# LS1C300B_176A_Msystem.net
KiCad netlist of a schematic drawn in Altium Designer
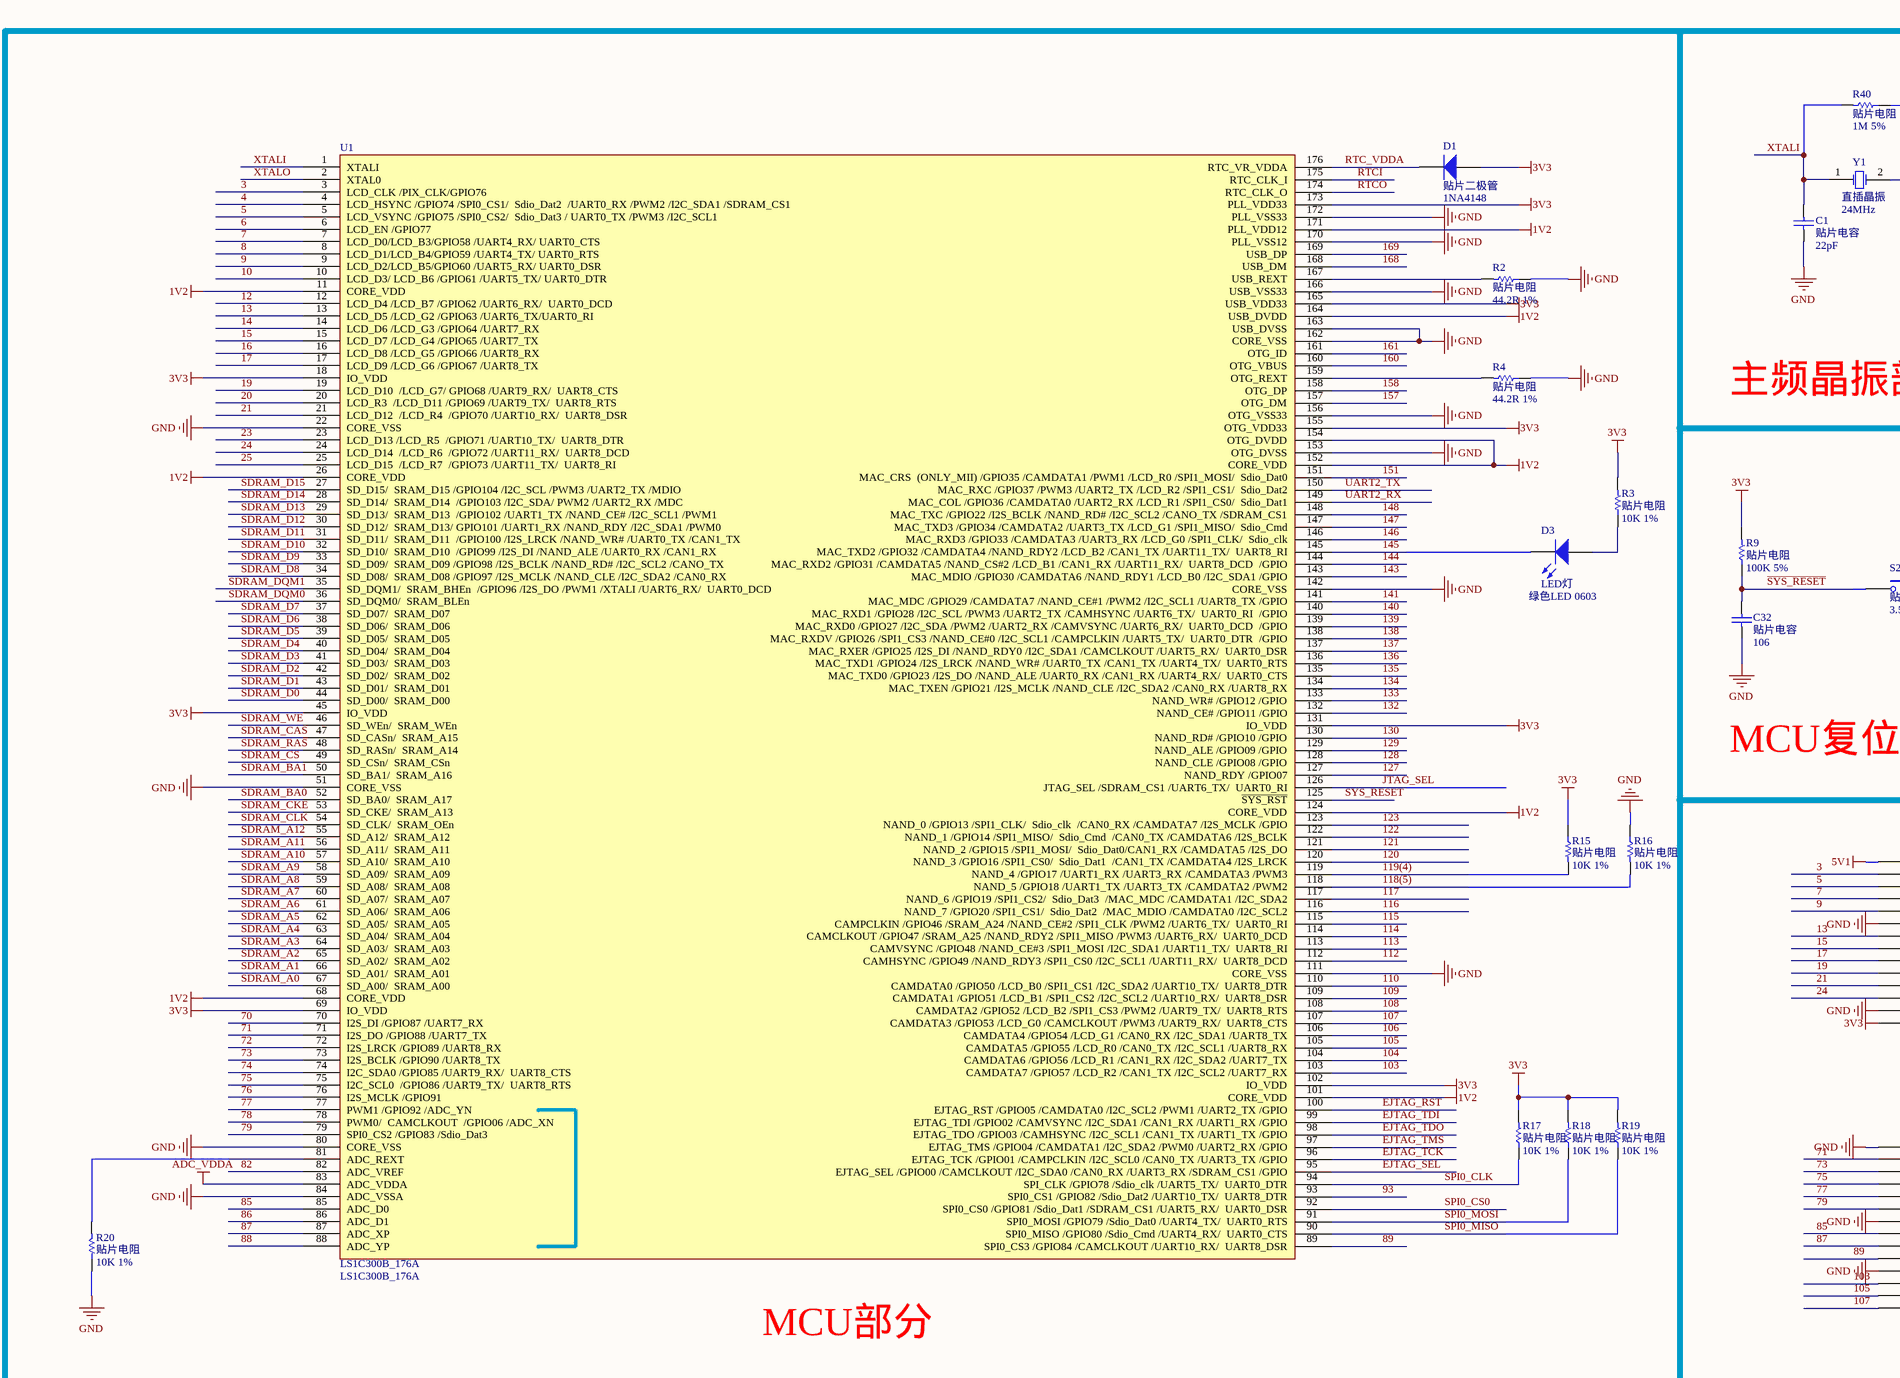
[diagram p0: LS1C300B_176A_Msystem.SchDoc, top left]
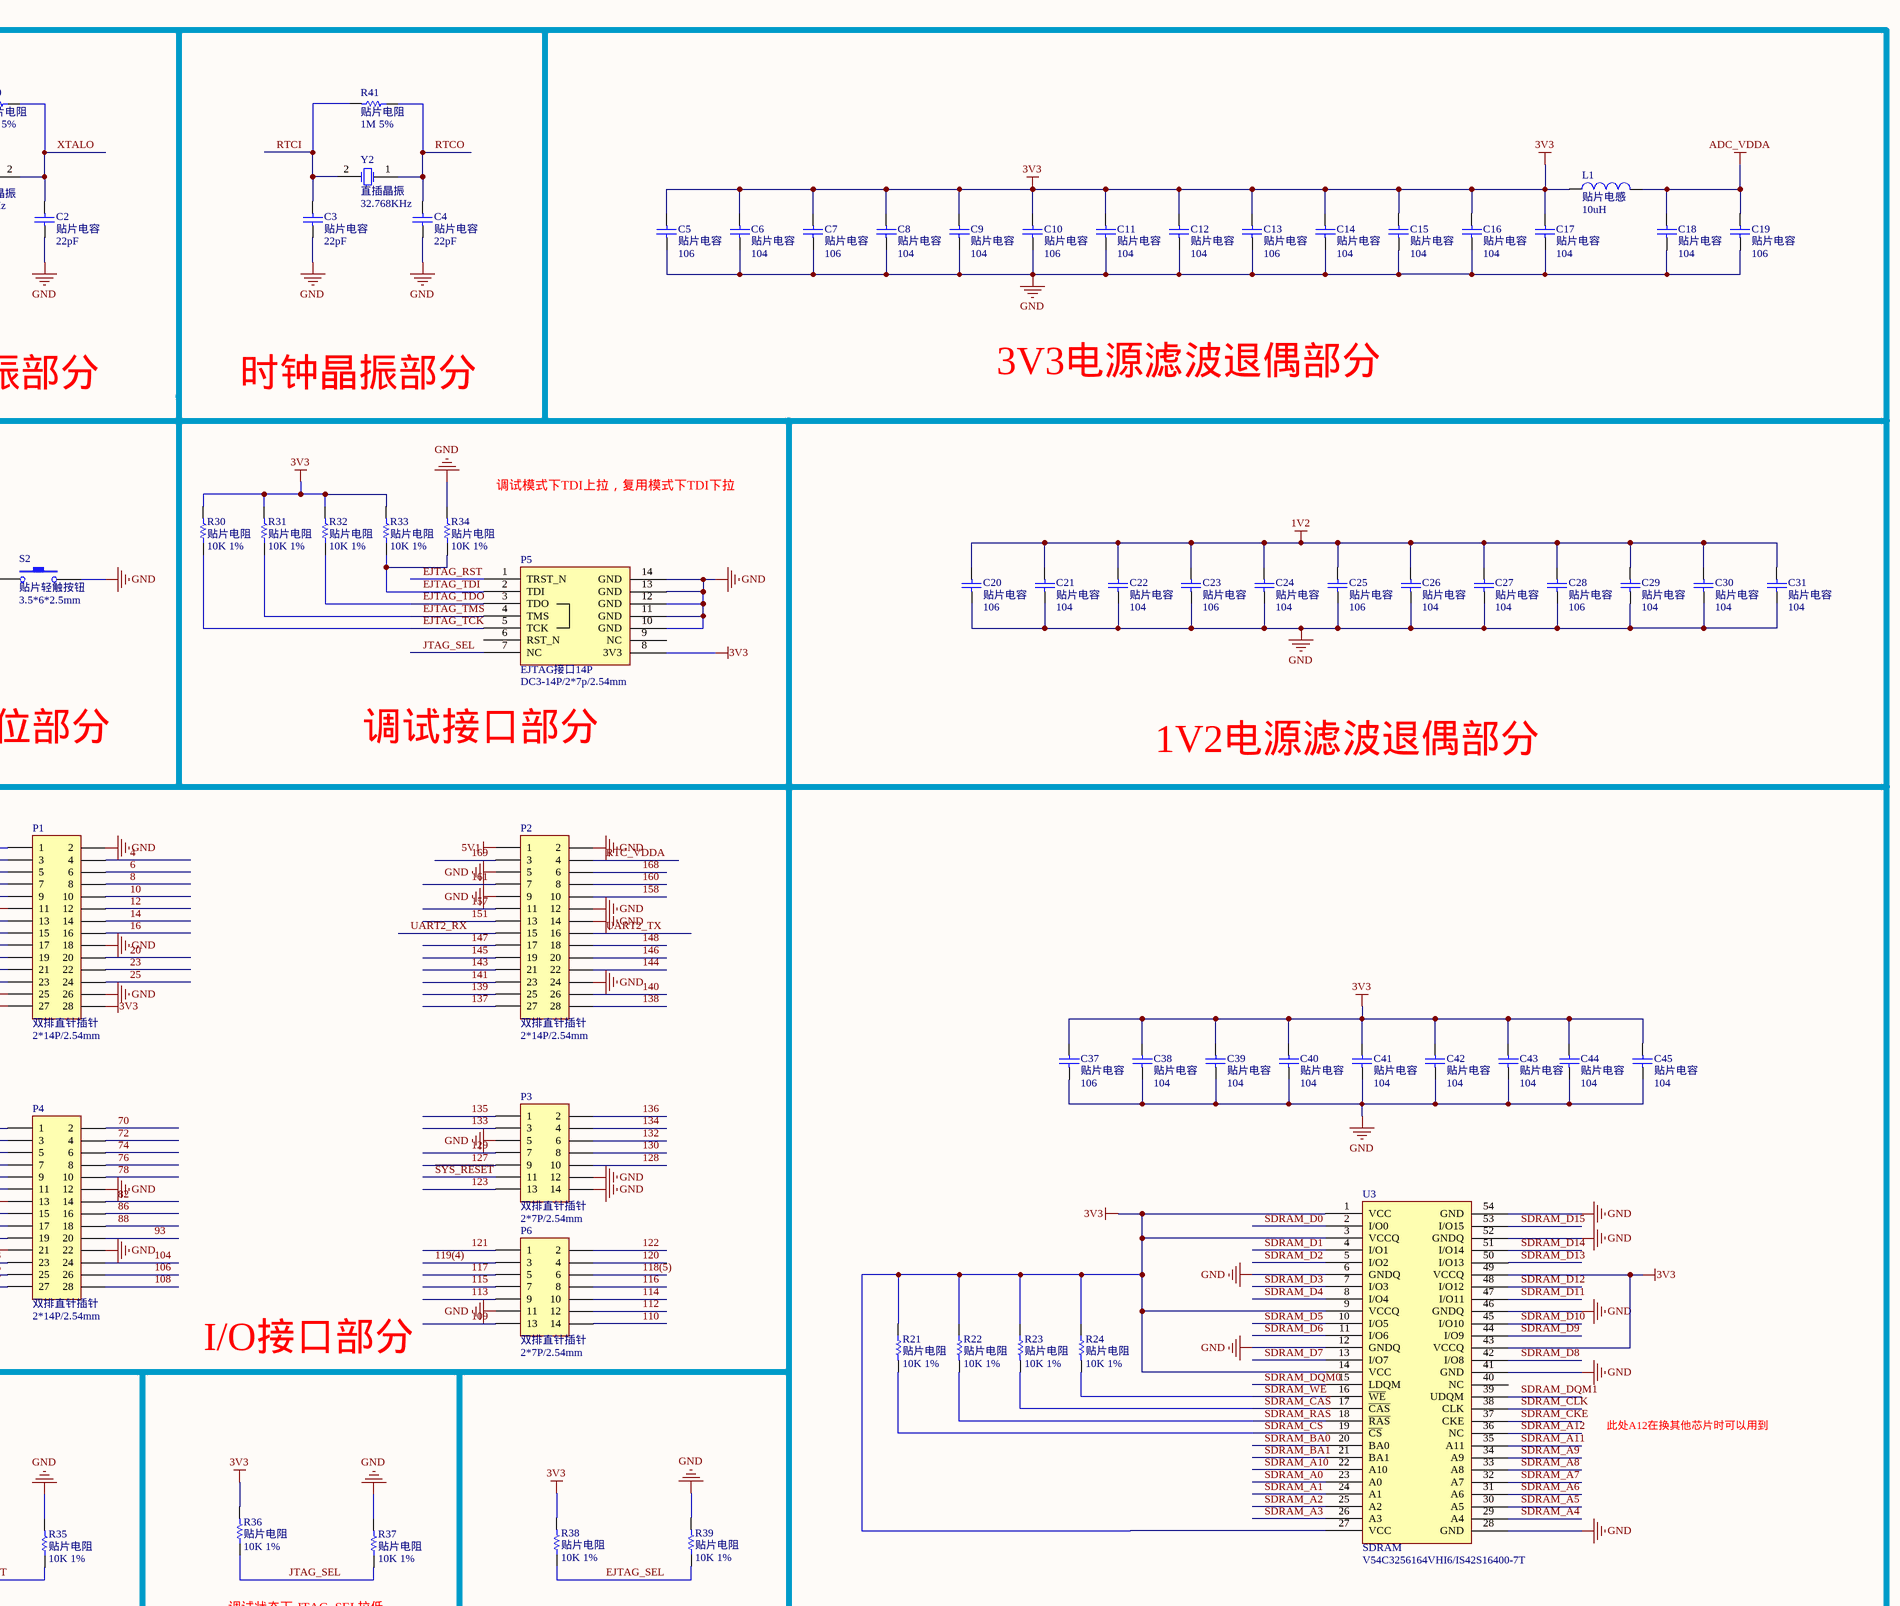
[diagram p1: LS1C300B_176A_Msystem.SchDoc, top right]
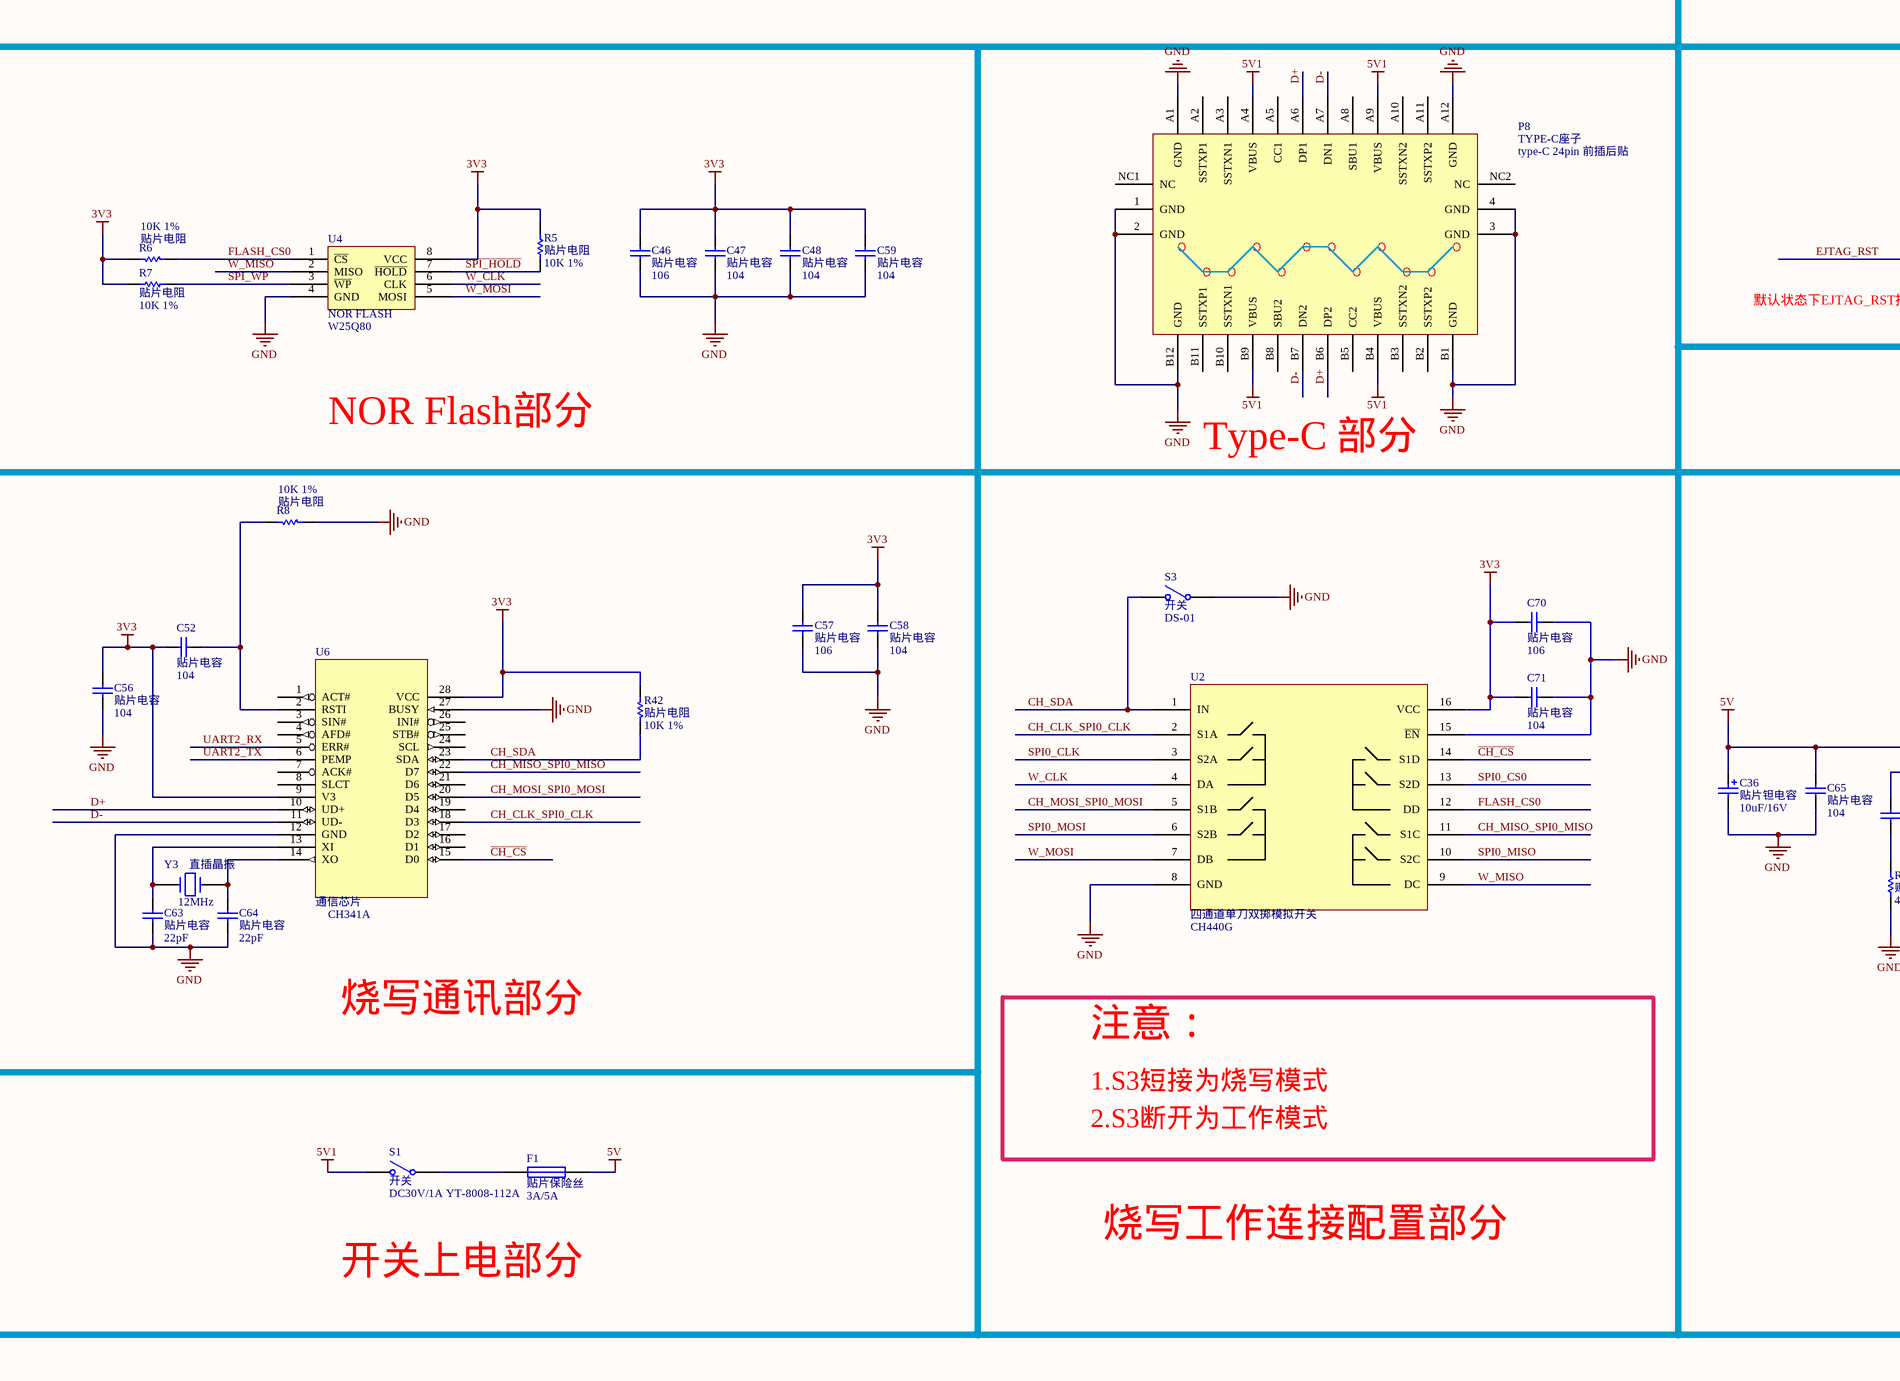
[diagram p2: LS1C300B_176A_Msystem.SchDoc, bottom left]
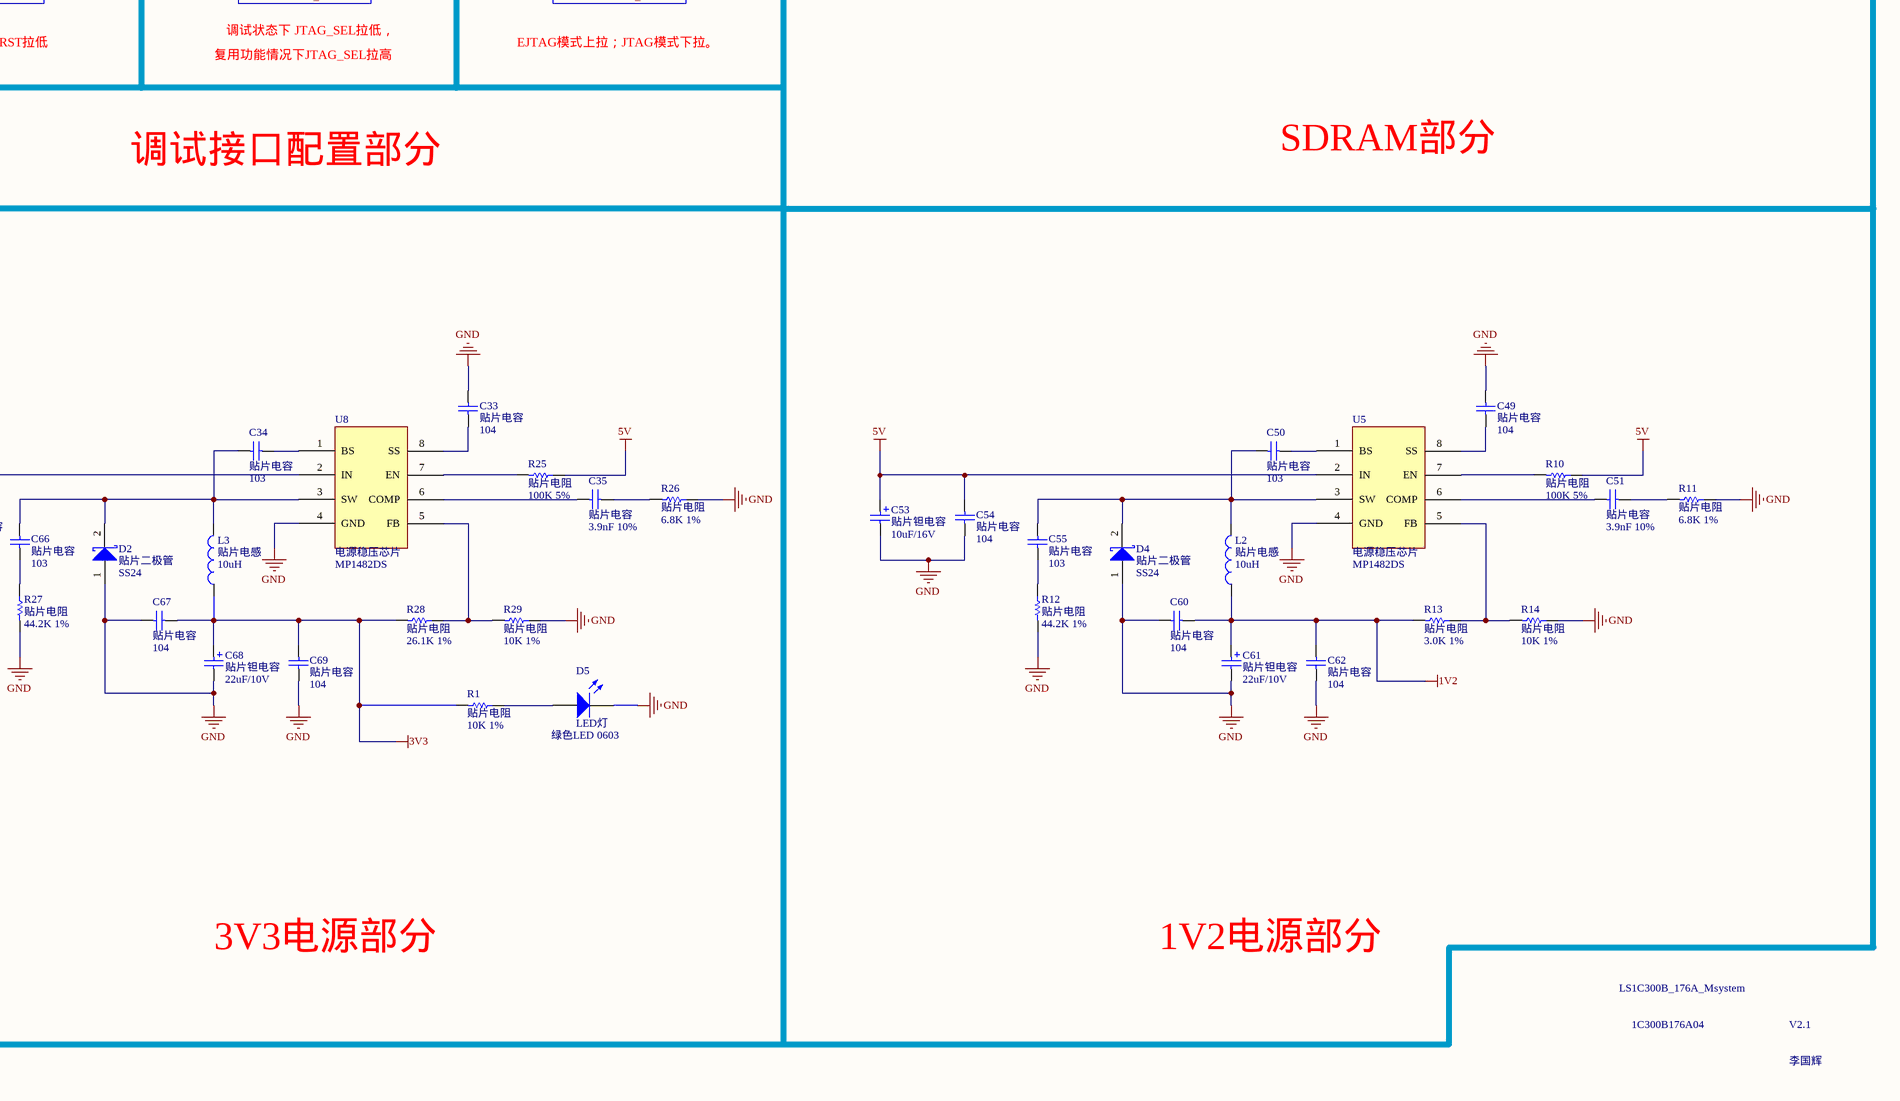
[diagram p3: LS1C300B_176A_Msystem.SchDoc, bottom right]

(export (version "E")
  (design (tool "Eeschema 10.0.6"))
  (components
    (comp (ref "C1")
      (value "贴片电容")
      (footprint "liguohui:C0603")
      (description "Capacitor")
      (fields (field (name "ALTIUM_VALUE") "22pF") (field (name "PUBLISHER") "Altium Limited"))
      (libsource (lib "Miscellaneous Devices") (part "Cap"))
    )
    (comp (ref "C2")
      (value "贴片电容")
      (footprint "liguohui:C0603")
      (description "Capacitor")
      (fields (field (name "ALTIUM_VALUE") "22pF") (field (name "PUBLISHER") "Altium Limited"))
      (libsource (lib "Miscellaneous Devices") (part "Cap"))
    )
    (comp (ref "C3")
      (value "贴片电容")
      (footprint "C0603")
      (description "Capacitor")
      (fields (field (name "ALTIUM_VALUE") "22pF") (field (name "PUBLISHER") "Altium Limited"))
      (libsource (lib "Miscellaneous Devices") (part "Cap"))
    )
    (comp (ref "C4")
      (value "贴片电容")
      (footprint "C0603")
      (description "Capacitor")
      (fields (field (name "ALTIUM_VALUE") "22pF") (field (name "PUBLISHER") "Altium Limited"))
      (libsource (lib "Miscellaneous Devices") (part "Cap"))
    )
    (comp (ref "C5")
      (value "贴片电容")
      (footprint "C0603")
      (description "Capacitor")
      (fields (field (name "ALTIUM_VALUE") "106") (field (name "PUBLISHER") "Altium Limited"))
      (libsource (lib "Miscellaneous Devices") (part "Cap"))
    )
    (comp (ref "C6")
      (value "贴片电容")
      (footprint "C0603")
      (description "Capacitor")
      (fields (field (name "ALTIUM_VALUE") "104") (field (name "PUBLISHER") "Altium Limited"))
      (libsource (lib "Miscellaneous Devices") (part "Cap"))
    )
    (comp (ref "C7")
      (value "贴片电容")
      (footprint "C0603")
      (description "Capacitor")
      (fields (field (name "ALTIUM_VALUE") "106") (field (name "PUBLISHER") "Altium Limited"))
      (libsource (lib "Miscellaneous Devices") (part "Cap"))
    )
    (comp (ref "C8")
      (value "贴片电容")
      (footprint "C0603")
      (description "Capacitor")
      (fields (field (name "ALTIUM_VALUE") "104") (field (name "PUBLISHER") "Altium Limited"))
      (libsource (lib "Miscellaneous Devices") (part "Cap"))
    )
    (comp (ref "C9")
      (value "贴片电容")
      (footprint "C0603")
      (description "Capacitor")
      (fields (field (name "ALTIUM_VALUE") "104") (field (name "PUBLISHER") "Altium Limited"))
      (libsource (lib "Miscellaneous Devices") (part "Cap"))
    )
    (comp (ref "C10")
      (value "贴片电容")
      (footprint "C0603")
      (description "Capacitor")
      (fields (field (name "ALTIUM_VALUE") "106") (field (name "PUBLISHER") "Altium Limited"))
      (libsource (lib "Miscellaneous Devices") (part "Cap"))
    )
    (comp (ref "C11")
      (value "贴片电容")
      (footprint "C0603")
      (description "Capacitor")
      (fields (field (name "ALTIUM_VALUE") "104") (field (name "PUBLISHER") "Altium Limited"))
      (libsource (lib "Miscellaneous Devices") (part "Cap"))
    )
    (comp (ref "C12")
      (value "贴片电容")
      (footprint "C0603")
      (description "Capacitor")
      (fields (field (name "ALTIUM_VALUE") "104") (field (name "PUBLISHER") "Altium Limited"))
      (libsource (lib "Miscellaneous Devices") (part "Cap"))
    )
    (comp (ref "C13")
      (value "贴片电容")
      (footprint "C0603")
      (description "Capacitor")
      (fields (field (name "ALTIUM_VALUE") "106") (field (name "PUBLISHER") "Altium Limited"))
      (libsource (lib "Miscellaneous Devices") (part "Cap"))
    )
    (comp (ref "C14")
      (value "贴片电容")
      (footprint "C0603")
      (description "Capacitor")
      (fields (field (name "ALTIUM_VALUE") "104") (field (name "PUBLISHER") "Altium Limited"))
      (libsource (lib "Miscellaneous Devices") (part "Cap"))
    )
    (comp (ref "C15")
      (value "贴片电容")
      (footprint "C0603")
      (description "Capacitor")
      (fields (field (name "ALTIUM_VALUE") "104") (field (name "PUBLISHER") "Altium Limited"))
      (libsource (lib "Miscellaneous Devices") (part "Cap"))
    )
    (comp (ref "C16")
      (value "贴片电容")
      (footprint "C0603")
      (description "Capacitor")
      (fields (field (name "ALTIUM_VALUE") "104") (field (name "PUBLISHER") "Altium Limited"))
      (libsource (lib "Miscellaneous Devices") (part "Cap"))
    )
    (comp (ref "C17")
      (value "贴片电容")
      (footprint "C0603")
      (description "Capacitor")
      (fields (field (name "ALTIUM_VALUE") "104") (field (name "PUBLISHER") "Altium Limited"))
      (libsource (lib "Miscellaneous Devices") (part "Cap"))
    )
    (comp (ref "C18")
      (value "贴片电容")
      (footprint "C0603")
      (description "Capacitor")
      (fields (field (name "ALTIUM_VALUE") "104") (field (name "PUBLISHER") "Altium Limited"))
      (libsource (lib "Miscellaneous Devices") (part "Cap"))
    )
    (comp (ref "C19")
      (value "贴片电容")
      (footprint "C0603")
      (description "Capacitor")
      (fields (field (name "ALTIUM_VALUE") "106") (field (name "PUBLISHER") "Altium Limited"))
      (libsource (lib "Miscellaneous Devices") (part "Cap"))
    )
    (comp (ref "C20")
      (value "贴片电容")
      (footprint "C0603")
      (description "Capacitor")
      (fields (field (name "ALTIUM_VALUE") "106") (field (name "PUBLISHER") "Altium Limited"))
      (libsource (lib "Miscellaneous Devices") (part "Cap"))
    )
    (comp (ref "C21")
      (value "贴片电容")
      (footprint "C0603")
      (description "Capacitor")
      (fields (field (name "ALTIUM_VALUE") "104") (field (name "PUBLISHER") "Altium Limited"))
      (libsource (lib "Miscellaneous Devices") (part "Cap"))
    )
    (comp (ref "C22")
      (value "贴片电容")
      (footprint "C0603")
      (description "Capacitor")
      (fields (field (name "ALTIUM_VALUE") "104") (field (name "PUBLISHER") "Altium Limited"))
      (libsource (lib "Miscellaneous Devices") (part "Cap"))
    )
    (comp (ref "C23")
      (value "贴片电容")
      (footprint "C0603")
      (description "Capacitor")
      (fields (field (name "ALTIUM_VALUE") "106") (field (name "PUBLISHER") "Altium Limited"))
      (libsource (lib "Miscellaneous Devices") (part "Cap"))
    )
    (comp (ref "C24")
      (value "贴片电容")
      (footprint "C0603")
      (description "Capacitor")
      (fields (field (name "ALTIUM_VALUE") "104") (field (name "PUBLISHER") "Altium Limited"))
      (libsource (lib "Miscellaneous Devices") (part "Cap"))
    )
    (comp (ref "C25")
      (value "贴片电容")
      (footprint "C0603")
      (description "Capacitor")
      (fields (field (name "ALTIUM_VALUE") "106") (field (name "PUBLISHER") "Altium Limited"))
      (libsource (lib "Miscellaneous Devices") (part "Cap"))
    )
    (comp (ref "C26")
      (value "贴片电容")
      (footprint "C0603")
      (description "Capacitor")
      (fields (field (name "ALTIUM_VALUE") "104") (field (name "PUBLISHER") "Altium Limited"))
      (libsource (lib "Miscellaneous Devices") (part "Cap"))
    )
    (comp (ref "C27")
      (value "贴片电容")
      (footprint "C0603")
      (description "Capacitor")
      (fields (field (name "ALTIUM_VALUE") "104") (field (name "PUBLISHER") "Altium Limited"))
      (libsource (lib "Miscellaneous Devices") (part "Cap"))
    )
    (comp (ref "C28")
      (value "贴片电容")
      (footprint "C0603")
      (description "Capacitor")
      (fields (field (name "ALTIUM_VALUE") "106") (field (name "PUBLISHER") "Altium Limited"))
      (libsource (lib "Miscellaneous Devices") (part "Cap"))
    )
    (comp (ref "C29")
      (value "贴片电容")
      (footprint "C0603")
      (description "Capacitor")
      (fields (field (name "ALTIUM_VALUE") "104") (field (name "PUBLISHER") "Altium Limited"))
      (libsource (lib "Miscellaneous Devices") (part "Cap"))
    )
    (comp (ref "C30")
      (value "贴片电容")
      (footprint "C0603")
      (description "Capacitor")
      (fields (field (name "ALTIUM_VALUE") "104") (field (name "PUBLISHER") "Altium Limited"))
      (libsource (lib "Miscellaneous Devices") (part "Cap"))
    )
    (comp (ref "C31")
      (value "贴片电容")
      (footprint "C0603")
      (description "Capacitor")
      (fields (field (name "ALTIUM_VALUE") "104") (field (name "PUBLISHER") "Altium Limited"))
      (libsource (lib "Miscellaneous Devices") (part "Cap"))
    )
    (comp (ref "C32")
      (value "贴片电容")
      (footprint "C0603")
      (description "Capacitor")
      (fields (field (name "ALTIUM_VALUE") "106") (field (name "PUBLISHER") "Altium Limited"))
      (libsource (lib "Miscellaneous Devices") (part "Cap"))
    )
    (comp (ref "C33")
      (value "贴片电容")
      (footprint "C0603")
      (description "Capacitor")
      (fields (field (name "ALTIUM_VALUE") "104") (field (name "PUBLISHER") "Altium Limited"))
      (libsource (lib "Miscellaneous Devices") (part "Cap"))
    )
    (comp (ref "C34")
      (value "贴片电容")
      (footprint "C0603")
      (description "Capacitor")
      (fields (field (name "ALTIUM_VALUE") "103") (field (name "PUBLISHER") "Altium Limited"))
      (libsource (lib "Miscellaneous Devices") (part "Cap"))
    )
    (comp (ref "C35")
      (value "贴片电容")
      (footprint "C0603")
      (description "Capacitor")
      (fields (field (name "ALTIUM_VALUE") "3.9nF 10%") (field (name "PUBLISHER") "Altium Limited"))
      (libsource (lib "Miscellaneous Devices") (part "Cap"))
    )
    (comp (ref "C36")
      (value "贴片钽电容")
      (footprint "P-C1206")
      (description "Polarized Capacitor (Axial)")
      (fields (field (name "ALTIUM_VALUE") "10uF/16V") (field (name "PUBLISHER") "Altium Limited"))
      (libsource (lib "Miscellaneous Devices") (part "Cap Pol2"))
    )
    (comp (ref "C37")
      (value "贴片电容")
      (footprint "C0603")
      (description "Capacitor")
      (fields (field (name "ALTIUM_VALUE") "106") (field (name "PUBLISHER") "Altium Limited"))
      (libsource (lib "Miscellaneous Devices") (part "Cap"))
    )
    (comp (ref "C38")
      (value "贴片电容")
      (footprint "C0603")
      (description "Capacitor")
      (fields (field (name "ALTIUM_VALUE") "104") (field (name "PUBLISHER") "Altium Limited"))
      (libsource (lib "Miscellaneous Devices") (part "Cap"))
    )
    (comp (ref "C39")
      (value "贴片电容")
      (footprint "C0603")
      (description "Capacitor")
      (fields (field (name "ALTIUM_VALUE") "104") (field (name "PUBLISHER") "Altium Limited"))
      (libsource (lib "Miscellaneous Devices") (part "Cap"))
    )
    (comp (ref "C40")
      (value "贴片电容")
      (footprint "C0603")
      (description "Capacitor")
      (fields (field (name "ALTIUM_VALUE") "104") (field (name "PUBLISHER") "Altium Limited"))
      (libsource (lib "Miscellaneous Devices") (part "Cap"))
    )
    (comp (ref "C41")
      (value "贴片电容")
      (footprint "C0603")
      (description "Capacitor")
      (fields (field (name "ALTIUM_VALUE") "104") (field (name "PUBLISHER") "Altium Limited"))
      (libsource (lib "Miscellaneous Devices") (part "Cap"))
    )
    (comp (ref "C42")
      (value "贴片电容")
      (footprint "C0603")
      (description "Capacitor")
      (fields (field (name "ALTIUM_VALUE") "104") (field (name "PUBLISHER") "Altium Limited"))
      (libsource (lib "Miscellaneous Devices") (part "Cap"))
    )
    (comp (ref "C43")
      (value "贴片电容")
      (footprint "C0603")
      (description "Capacitor")
      (fields (field (name "ALTIUM_VALUE") "104") (field (name "PUBLISHER") "Altium Limited"))
      (libsource (lib "Miscellaneous Devices") (part "Cap"))
    )
    (comp (ref "C44")
      (value "贴片电容")
      (footprint "C0603")
      (description "Capacitor")
      (fields (field (name "ALTIUM_VALUE") "104") (field (name "PUBLISHER") "Altium Limited"))
      (libsource (lib "Miscellaneous Devices") (part "Cap"))
    )
    (comp (ref "C45")
      (value "贴片电容")
      (footprint "C0603")
      (description "Capacitor")
      (fields (field (name "ALTIUM_VALUE") "104") (field (name "PUBLISHER") "Altium Limited"))
      (libsource (lib "Miscellaneous Devices") (part "Cap"))
    )
    (comp (ref "C46")
      (value "贴片电容")
      (footprint "C0603")
      (description "Capacitor")
      (fields (field (name "ALTIUM_VALUE") "106") (field (name "PUBLISHER") "Altium Limited"))
      (libsource (lib "Miscellaneous Devices") (part "Cap"))
    )
    (comp (ref "C47")
      (value "贴片电容")
      (footprint "C0603")
      (description "Capacitor")
      (fields (field (name "ALTIUM_VALUE") "104") (field (name "PUBLISHER") "Altium Limited"))
      (libsource (lib "Miscellaneous Devices") (part "Cap"))
    )
    (comp (ref "C48")
      (value "贴片电容")
      (footprint "C0603")
      (description "Capacitor")
      (fields (field (name "ALTIUM_VALUE") "104") (field (name "PUBLISHER") "Altium Limited"))
      (libsource (lib "Miscellaneous Devices") (part "Cap"))
    )
    (comp (ref "C49")
      (value "贴片电容")
      (footprint "C0603")
      (description "Capacitor")
      (fields (field (name "ALTIUM_VALUE") "104") (field (name "PUBLISHER") "Altium Limited"))
      (libsource (lib "Miscellaneous Devices") (part "Cap"))
    )
    (comp (ref "C50")
      (value "贴片电容")
      (footprint "C0603")
      (description "Capacitor")
      (fields (field (name "ALTIUM_VALUE") "103") (field (name "PUBLISHER") "Altium Limited"))
      (libsource (lib "Miscellaneous Devices") (part "Cap"))
    )
    (comp (ref "C51")
      (value "贴片电容")
      (footprint "C0603")
      (description "Capacitor")
      (fields (field (name "ALTIUM_VALUE") "3.9nF 10%") (field (name "PUBLISHER") "Altium Limited"))
      (libsource (lib "Miscellaneous Devices") (part "Cap"))
    )
    (comp (ref "C52")
      (value "贴片电容")
      (footprint "C0603")
      (description "Capacitor")
      (fields (field (name "ALTIUM_VALUE") "104") (field (name "PUBLISHER") "Altium Limited"))
      (libsource (lib "Miscellaneous Devices") (part "Cap"))
    )
    (comp (ref "C53")
      (value "贴片钽电容")
      (footprint "P-C1206")
      (description "Polarized Capacitor (Axial)")
      (fields (field (name "ALTIUM_VALUE") "10uF/16V") (field (name "PUBLISHER") "Altium Limited"))
      (libsource (lib "Miscellaneous Devices") (part "Cap Pol2"))
    )
    (comp (ref "C54")
      (value "贴片电容")
      (footprint "C0603")
      (description "Capacitor")
      (fields (field (name "ALTIUM_VALUE") "104") (field (name "PUBLISHER") "Altium Limited"))
      (libsource (lib "Miscellaneous Devices") (part "Cap"))
    )
    (comp (ref "C55")
      (value "贴片电容")
      (footprint "C0603")
      (description "Capacitor")
      (fields (field (name "ALTIUM_VALUE") "103") (field (name "PUBLISHER") "Altium Limited"))
      (libsource (lib "Miscellaneous Devices") (part "Cap"))
    )
    (comp (ref "C56")
      (value "贴片电容")
      (footprint "C0603")
      (description "Capacitor")
      (fields (field (name "ALTIUM_VALUE") "104") (field (name "PUBLISHER") "Altium Limited"))
      (libsource (lib "Miscellaneous Devices") (part "Cap"))
    )
    (comp (ref "C57")
      (value "贴片电容")
      (footprint "C0603")
      (description "Capacitor")
      (fields (field (name "ALTIUM_VALUE") "106") (field (name "PUBLISHER") "Altium Limited"))
      (libsource (lib "Miscellaneous Devices") (part "Cap"))
    )
    (comp (ref "C58")
      (value "贴片电容")
      (footprint "C0603")
      (description "Capacitor")
      (fields (field (name "ALTIUM_VALUE") "104") (field (name "PUBLISHER") "Altium Limited"))
      (libsource (lib "Miscellaneous Devices") (part "Cap"))
    )
    (comp (ref "C59")
      (value "贴片电容")
      (footprint "C0603")
      (description "Capacitor")
      (fields (field (name "ALTIUM_VALUE") "104") (field (name "PUBLISHER") "Altium Limited"))
      (libsource (lib "Miscellaneous Devices") (part "Cap"))
    )
    (comp (ref "C60")
      (value "贴片电容")
      (footprint "C0603")
      (description "Capacitor")
      (fields (field (name "ALTIUM_VALUE") "104") (field (name "PUBLISHER") "Altium Limited"))
      (libsource (lib "Miscellaneous Devices") (part "Cap"))
    )
    (comp (ref "C61")
      (value "贴片钽电容")
      (footprint "P-C1206")
      (description "Polarized Capacitor (Axial)")
      (fields (field (name "ALTIUM_VALUE") "22uF/10V") (field (name "PUBLISHER") "Altium Limited"))
      (libsource (lib "Miscellaneous Devices") (part "Cap Pol2"))
    )
    (comp (ref "C62")
      (value "贴片电容")
      (footprint "C0603")
      (description "Capacitor")
      (fields (field (name "ALTIUM_VALUE") "104") (field (name "PUBLISHER") "Altium Limited"))
      (libsource (lib "Miscellaneous Devices") (part "Cap"))
    )
    (comp (ref "C63")
      (value "贴片电容")
      (footprint "C0603")
      (description "Capacitor")
      (fields (field (name "ALTIUM_VALUE") "22pF") (field (name "PUBLISHER") "Altium Limited"))
      (libsource (lib "Miscellaneous Devices") (part "Cap"))
    )
    (comp (ref "C64")
      (value "贴片电容")
      (footprint "liguohui:C0603")
      (description "Capacitor")
      (fields (field (name "ALTIUM_VALUE") "22pF") (field (name "PUBLISHER") "Altium Limited"))
      (libsource (lib "Miscellaneous Devices") (part "Cap"))
    )
    (comp (ref "C65")
      (value "贴片电容")
      (footprint "C0603")
      (description "Capacitor")
      (fields (field (name "ALTIUM_VALUE") "104") (field (name "PUBLISHER") "Altium Limited"))
      (libsource (lib "Miscellaneous Devices") (part "Cap"))
    )
    (comp (ref "C66")
      (value "贴片电容")
      (footprint "C0603")
      (description "Capacitor")
      (fields (field (name "ALTIUM_VALUE") "103") (field (name "PUBLISHER") "Altium Limited"))
      (libsource (lib "Miscellaneous Devices") (part "Cap"))
    )
    (comp (ref "C67")
      (value "贴片电容")
      (footprint "C0603")
      (description "Capacitor")
      (fields (field (name "ALTIUM_VALUE") "104") (field (name "PUBLISHER") "Altium Limited"))
      (libsource (lib "Miscellaneous Devices") (part "Cap"))
    )
    (comp (ref "C68")
      (value "贴片钽电容")
      (footprint "P-C1206")
      (description "Polarized Capacitor (Axial)")
      (fields (field (name "ALTIUM_VALUE") "22uF/10V") (field (name "PUBLISHER") "Altium Limited"))
      (libsource (lib "Miscellaneous Devices") (part "Cap Pol2"))
    )
    (comp (ref "C69")
      (value "贴片电容")
      (footprint "C0603")
      (description "Capacitor")
      (fields (field (name "ALTIUM_VALUE") "104") (field (name "PUBLISHER") "Altium Limited"))
      (libsource (lib "Miscellaneous Devices") (part "Cap"))
    )
    (comp (ref "C70")
      (value "贴片电容")
      (footprint "C0603")
      (description "Capacitor")
      (fields (field (name "ALTIUM_VALUE") "106") (field (name "PUBLISHER") "Altium Limited"))
      (libsource (lib "Miscellaneous Devices") (part "Cap"))
    )
    (comp (ref "C71")
      (value "贴片电容")
      (footprint "C0603")
      (description "Capacitor")
      (fields (field (name "ALTIUM_VALUE") "104") (field (name "PUBLISHER") "Altium Limited"))
      (libsource (lib "Miscellaneous Devices") (part "Cap"))
    )
    (comp (ref "D1")
      (value "贴片二极管")
      (footprint "LL-34")
      (description "Default Diode")
      (fields (field (name "ALTIUM_VALUE") "1NA4148") (field (name "PUBLISHER") "Altium Limited"))
      (libsource (lib "Miscellaneous Devices") (part "Diode"))
    )
    (comp (ref "D2")
      (value "贴片二极管")
      (footprint "DO-214AC")
      (fields (field (name "ALTIUM_VALUE") "SS24"))
      (libsource (lib "LGHLIB") (part "1N47xx"))
    )
    (comp (ref "D3")
      (value "LED灯")
      (footprint "LED-0603")
      (description "Typical INFRARED GaAs LED")
      (fields (field (name "ALTIUM_VALUE") "绿色LED 0603") (field (name "PUBLISHER") "Altium Limited"))
      (libsource (lib "Miscellaneous Devices") (part "LED0"))
    )
    (comp (ref "D4")
      (value "贴片二极管")
      (footprint "DO-214AC")
      (fields (field (name "ALTIUM_VALUE") "SS24"))
      (libsource (lib "LGHLIB") (part "1N47xx"))
    )
    (comp (ref "D5")
      (value "LED灯")
      (footprint "LED-0603")
      (description "Typical INFRARED GaAs LED")
      (fields (field (name "ALTIUM_VALUE") "绿色LED 0603") (field (name "PUBLISHER") "Altium Limited"))
      (libsource (lib "Miscellaneous Devices") (part "LED0"))
    )
    (comp (ref "F1")
      (value "贴片保险丝")
      (footprint "R1206")
      (description "Fuse")
      (fields (field (name "ALTIUM_VALUE") "3A/5A") (field (name "PUBLISHER") "Altium Limited"))
      (libsource (lib "Miscellaneous Devices") (part "Fuse 1"))
    )
    (comp (ref "L1")
      (value "贴片电感")
      (footprint "L0603")
      (description "Inductor")
      (fields (field (name "ALTIUM_VALUE") "10uH") (field (name "PUBLISHER") "Altium Limited"))
      (libsource (lib "Miscellaneous Devices") (part "Inductor"))
    )
    (comp (ref "L2")
      (value "贴片电感")
      (footprint "CD75")
      (description "Inductor")
      (fields (field (name "ALTIUM_VALUE") "10uH") (field (name "PUBLISHER") "Altium Limited"))
      (libsource (lib "Miscellaneous Devices") (part "Inductor"))
    )
    (comp (ref "L3")
      (value "贴片电感")
      (footprint "CD75")
      (description "Inductor")
      (fields (field (name "ALTIUM_VALUE") "10uH") (field (name "PUBLISHER") "Altium Limited"))
      (libsource (lib "Miscellaneous Devices") (part "Inductor"))
    )
    (comp (ref "P1")
      (value "双排直针插针")
      (footprint "HDR2X14")
      (description "Header, 14-Pin, Dual row")
      (fields (field (name "ALTIUM_VALUE") "2*14P/2.54mm") (field (name "PUBLISHER") "Altium Limited"))
      (libsource (lib "Miscellaneous Connectors") (part "MHDR2X14"))
    )
    (comp (ref "P2")
      (value "双排直针插针")
      (footprint "HDR2X14")
      (description "Header, 14-Pin, Dual row")
      (fields (field (name "ALTIUM_VALUE") "2*14P/2.54mm") (field (name "PUBLISHER") "Altium Limited"))
      (libsource (lib "Miscellaneous Connectors") (part "MHDR2X14"))
    )
    (comp (ref "P3")
      (value "双排直针插针")
      (footprint "HDR2X7")
      (description "Header, 7-Pin, Dual row")
      (fields (field (name "ALTIUM_VALUE") "2*7P/2.54mm") (field (name "PUBLISHER") "Altium Limited"))
      (libsource (lib "Miscellaneous Connectors") (part "MHDR2X7"))
    )
    (comp (ref "P4")
      (value "双排直针插针")
      (footprint "HDR2X14")
      (description "Header, 14-Pin, Dual row")
      (fields (field (name "ALTIUM_VALUE") "2*14P/2.54mm") (field (name "PUBLISHER") "Altium Limited"))
      (libsource (lib "Miscellaneous Connectors") (part "MHDR2X14"))
    )
    (comp (ref "P5")
      (value "EJTAG接口14P")
      (footprint "DC3-14P")
      (fields (field (name "ALTIUM_VALUE") "DC3-14P/2*7p/2.54mm"))
      (libsource (lib "LGHLIB") (part "EJTAG-14P"))
    )
    (comp (ref "P6")
      (value "双排直针插针")
      (footprint "HDR2X7")
      (description "Header, 7-Pin, Dual row")
      (fields (field (name "ALTIUM_VALUE") "2*7P/2.54mm") (field (name "PUBLISHER") "Altium Limited"))
      (libsource (lib "Miscellaneous Connectors") (part "MHDR2X7"))
    )
    (comp (ref "P8")
      (value "TYPE-C座子")
      (footprint "Type-C-24pin")
      (description "TYPE-C座子，24pin ，可用于大电流，四脚插板，前插后贴")
      (fields (field (name "ALTIUM_VALUE") "type-C 24pin 前插后贴"))
      (libsource (lib "LGHLIB") (part "Type-C-24PIN"))
    )
    (comp (ref "R1")
      (value "贴片电阻")
      (footprint "R0603")
      (description "Resistor")
      (fields (field (name "ALTIUM_VALUE") "10K 1%") (field (name "PUBLISHER") "Altium Limited"))
      (libsource (lib "Miscellaneous Devices") (part "Res1"))
    )
    (comp (ref "R2")
      (value "贴片电阻")
      (footprint "R0603")
      (description "Resistor")
      (fields (field (name "ALTIUM_VALUE") "44.2R 1%") (field (name "PUBLISHER") "Altium Limited"))
      (libsource (lib "Miscellaneous Devices") (part "Res1"))
    )
    (comp (ref "R3")
      (value "贴片电阻")
      (footprint "R0603")
      (description "Resistor")
      (fields (field (name "ALTIUM_VALUE") "10K 1%") (field (name "PUBLISHER") "Altium Limited"))
      (libsource (lib "Miscellaneous Devices") (part "Res1"))
    )
    (comp (ref "R4")
      (value "贴片电阻")
      (footprint "R0603")
      (description "Resistor")
      (fields (field (name "ALTIUM_VALUE") "44.2R 1%") (field (name "PUBLISHER") "Altium Limited"))
      (libsource (lib "Miscellaneous Devices") (part "Res1"))
    )
    (comp (ref "R5")
      (value "贴片电阻")
      (footprint "R0603")
      (description "Resistor")
      (fields (field (name "ALTIUM_VALUE") "10K 1%") (field (name "PUBLISHER") "Altium Limited"))
      (libsource (lib "Miscellaneous Devices") (part "Res1"))
    )
    (comp (ref "R6")
      (value "贴片电阻")
      (footprint "R0603")
      (description "Resistor")
      (fields (field (name "ALTIUM_VALUE") "10K 1%") (field (name "PUBLISHER") "Altium Limited"))
      (libsource (lib "Miscellaneous Devices") (part "Res1"))
    )
    (comp (ref "R7")
      (value "贴片电阻")
      (footprint "R0603")
      (description "Resistor")
      (fields (field (name "ALTIUM_VALUE") "10K 1%") (field (name "PUBLISHER") "Altium Limited"))
      (libsource (lib "Miscellaneous Devices") (part "Res1"))
    )
    (comp (ref "R8")
      (value "贴片电阻")
      (footprint "R0603")
      (description "Resistor")
      (fields (field (name "ALTIUM_VALUE") "10K 1%") (field (name "PUBLISHER") "Altium Limited"))
      (libsource (lib "Miscellaneous Devices") (part "Res1"))
    )
    (comp (ref "R9")
      (value "贴片电阻")
      (footprint "R0603")
      (description "Resistor")
      (fields (field (name "ALTIUM_VALUE") "100K 5%") (field (name "PUBLISHER") "Altium Limited"))
      (libsource (lib "Miscellaneous Devices") (part "Res1"))
    )
    (comp (ref "R10")
      (value "贴片电阻")
      (footprint "R0603")
      (description "Resistor")
      (fields (field (name "ALTIUM_VALUE") "100K 5%") (field (name "PUBLISHER") "Altium Limited"))
      (libsource (lib "Miscellaneous Devices") (part "Res1"))
    )
    (comp (ref "R11")
      (value "贴片电阻")
      (footprint "R0603")
      (description "Resistor")
      (fields (field (name "ALTIUM_VALUE") "6.8K 1%") (field (name "PUBLISHER") "Altium Limited"))
      (libsource (lib "Miscellaneous Devices") (part "Res1"))
    )
    (comp (ref "R12")
      (value "贴片电阻")
      (footprint "R0603")
      (description "Resistor")
      (fields (field (name "ALTIUM_VALUE") "44.2K 1%") (field (name "PUBLISHER") "Altium Limited"))
      (libsource (lib "Miscellaneous Devices") (part "Res1"))
    )
    (comp (ref "R13")
      (value "贴片电阻")
      (footprint "R0603")
      (description "Resistor")
      (fields (field (name "ALTIUM_VALUE") "3.0K 1%") (field (name "PUBLISHER") "Altium Limited"))
      (libsource (lib "Miscellaneous Devices") (part "Res1"))
    )
    (comp (ref "R14")
      (value "贴片电阻")
      (footprint "R0603")
      (description "Resistor")
      (fields (field (name "ALTIUM_VALUE") "10K 1%") (field (name "PUBLISHER") "Altium Limited"))
      (libsource (lib "Miscellaneous Devices") (part "Res1"))
    )
    (comp (ref "R15")
      (value "贴片电阻")
      (footprint "R0603")
      (description "Resistor")
      (fields (field (name "ALTIUM_VALUE") "10K 1%") (field (name "PUBLISHER") "Altium Limited"))
      (libsource (lib "Miscellaneous Devices") (part "Res1"))
    )
    (comp (ref "R16")
      (value "贴片电阻")
      (footprint "R0603")
      (description "Resistor")
      (fields (field (name "ALTIUM_VALUE") "10K 1%") (field (name "PUBLISHER") "Altium Limited"))
      (libsource (lib "Miscellaneous Devices") (part "Res1"))
    )
    (comp (ref "R17")
      (value "贴片电阻")
      (footprint "R0603")
      (description "Resistor")
      (fields (field (name "ALTIUM_VALUE") "10K 1%") (field (name "PUBLISHER") "Altium Limited"))
      (libsource (lib "Miscellaneous Devices") (part "Res1"))
    )
    (comp (ref "R18")
      (value "贴片电阻")
      (footprint "R0603")
      (description "Resistor")
      (fields (field (name "ALTIUM_VALUE") "10K 1%") (field (name "PUBLISHER") "Altium Limited"))
      (libsource (lib "Miscellaneous Devices") (part "Res1"))
    )
    (comp (ref "R19")
      (value "贴片电阻")
      (footprint "R0603")
      (description "Resistor")
      (fields (field (name "ALTIUM_VALUE") "10K 1%") (field (name "PUBLISHER") "Altium Limited"))
      (libsource (lib "Miscellaneous Devices") (part "Res1"))
    )
    (comp (ref "R20")
      (value "贴片电阻")
      (footprint "R0603")
      (description "Resistor")
      (fields (field (name "ALTIUM_VALUE") "10K 1%") (field (name "PUBLISHER") "Altium Limited"))
      (libsource (lib "Miscellaneous Devices") (part "Res1"))
    )
    (comp (ref "R21")
      (value "贴片电阻")
      (footprint "R0603")
      (description "Resistor")
      (fields (field (name "ALTIUM_VALUE") "10K 1%") (field (name "PUBLISHER") "Altium Limited"))
      (libsource (lib "Miscellaneous Devices") (part "Res1"))
    )
    (comp (ref "R22")
      (value "贴片电阻")
      (footprint "R0603")
      (description "Resistor")
      (fields (field (name "ALTIUM_VALUE") "10K 1%") (field (name "PUBLISHER") "Altium Limited"))
      (libsource (lib "Miscellaneous Devices") (part "Res1"))
    )
    (comp (ref "R23")
      (value "贴片电阻")
      (footprint "R0603")
      (description "Resistor")
      (fields (field (name "ALTIUM_VALUE") "10K 1%") (field (name "PUBLISHER") "Altium Limited"))
      (libsource (lib "Miscellaneous Devices") (part "Res1"))
    )
    (comp (ref "R24")
      (value "贴片电阻")
      (footprint "R0603")
      (description "Resistor")
      (fields (field (name "ALTIUM_VALUE") "10K 1%") (field (name "PUBLISHER") "Altium Limited"))
      (libsource (lib "Miscellaneous Devices") (part "Res1"))
    )
    (comp (ref "R25")
      (value "贴片电阻")
      (footprint "R0603")
      (description "Resistor")
      (fields (field (name "ALTIUM_VALUE") "100K 5%") (field (name "PUBLISHER") "Altium Limited"))
      (libsource (lib "Miscellaneous Devices") (part "Res1"))
    )
    (comp (ref "R26")
      (value "贴片电阻")
      (footprint "R0603")
      (description "Resistor")
      (fields (field (name "ALTIUM_VALUE") "6.8K 1%") (field (name "PUBLISHER") "Altium Limited"))
      (libsource (lib "Miscellaneous Devices") (part "Res1"))
    )
    (comp (ref "R27")
      (value "贴片电阻")
      (footprint "R0603")
      (description "Resistor")
      (fields (field (name "ALTIUM_VALUE") "44.2K 1%") (field (name "PUBLISHER") "Altium Limited"))
      (libsource (lib "Miscellaneous Devices") (part "Res1"))
    )
    (comp (ref "R28")
      (value "贴片电阻")
      (footprint "R0603")
      (description "Resistor")
      (fields (field (name "ALTIUM_VALUE") "26.1K 1%") (field (name "PUBLISHER") "Altium Limited"))
      (libsource (lib "Miscellaneous Devices") (part "Res1"))
    )
    (comp (ref "R29")
      (value "贴片电阻")
      (footprint "R0603")
      (description "Resistor")
      (fields (field (name "ALTIUM_VALUE") "10K 1%") (field (name "PUBLISHER") "Altium Limited"))
      (libsource (lib "Miscellaneous Devices") (part "Res1"))
    )
    (comp (ref "R30")
      (value "贴片电阻")
      (footprint "R0603")
      (description "Resistor")
      (fields (field (name "ALTIUM_VALUE") "10K 1%") (field (name "PUBLISHER") "Altium Limited"))
      (libsource (lib "Miscellaneous Devices") (part "Res1"))
    )
    (comp (ref "R31")
      (value "贴片电阻")
      (footprint "R0603")
      (description "Resistor")
      (fields (field (name "ALTIUM_VALUE") "10K 1%") (field (name "PUBLISHER") "Altium Limited"))
      (libsource (lib "Miscellaneous Devices") (part "Res1"))
    )
    (comp (ref "R32")
      (value "贴片电阻")
      (footprint "R0603")
      (description "Resistor")
      (fields (field (name "ALTIUM_VALUE") "10K 1%") (field (name "PUBLISHER") "Altium Limited"))
      (libsource (lib "Miscellaneous Devices") (part "Res1"))
    )
    (comp (ref "R33")
      (value "贴片电阻")
      (footprint "R0603")
      (description "Resistor")
      (fields (field (name "ALTIUM_VALUE") "10K 1%") (field (name "PUBLISHER") "Altium Limited"))
      (libsource (lib "Miscellaneous Devices") (part "Res1"))
    )
    (comp (ref "R34")
      (value "贴片电阻")
      (footprint "R0603")
      (description "Resistor")
      (fields (field (name "ALTIUM_VALUE") "10K 1%") (field (name "PUBLISHER") "Altium Limited"))
      (libsource (lib "Miscellaneous Devices") (part "Res1"))
    )
    (comp (ref "R35")
      (value "贴片电阻")
      (footprint "R0603")
      (description "Resistor")
      (fields (field (name "ALTIUM_VALUE") "10K 1%") (field (name "PUBLISHER") "Altium Limited"))
      (libsource (lib "Miscellaneous Devices") (part "Res1"))
    )
    (comp (ref "R36")
      (value "贴片电阻")
      (footprint "R0603")
      (description "Resistor")
      (fields (field (name "ALTIUM_VALUE") "10K 1%") (field (name "PUBLISHER") "Altium Limited"))
      (libsource (lib "Miscellaneous Devices") (part "Res1"))
    )
    (comp (ref "R37")
      (value "贴片电阻")
      (footprint "R0603")
      (description "Resistor")
      (fields (field (name "ALTIUM_VALUE") "10K 1%") (field (name "PUBLISHER") "Altium Limited"))
      (libsource (lib "Miscellaneous Devices") (part "Res1"))
    )
    (comp (ref "R38")
      (value "贴片电阻")
      (footprint "R0603")
      (description "Resistor")
      (fields (field (name "ALTIUM_VALUE") "10K 1%") (field (name "PUBLISHER") "Altium Limited"))
      (libsource (lib "Miscellaneous Devices") (part "Res1"))
    )
    (comp (ref "R39")
      (value "贴片电阻")
      (footprint "R0603")
      (description "Resistor")
      (fields (field (name "ALTIUM_VALUE") "10K 1%") (field (name "PUBLISHER") "Altium Limited"))
      (libsource (lib "Miscellaneous Devices") (part "Res1"))
    )
    (comp (ref "R40")
      (value "贴片电阻")
      (footprint "R0603")
      (description "Resistor")
      (fields (field (name "ALTIUM_VALUE") "1M 5%") (field (name "PUBLISHER") "Altium Limited"))
      (libsource (lib "Miscellaneous Devices") (part "Res1"))
    )
    (comp (ref "R41")
      (value "贴片电阻")
      (footprint "R0603")
      (description "Resistor")
      (fields (field (name "ALTIUM_VALUE") "1M 5%") (field (name "PUBLISHER") "Altium Limited"))
      (libsource (lib "Miscellaneous Devices") (part "Res1"))
    )
    (comp (ref "R42")
      (value "贴片电阻")
      (footprint "R0603")
      (description "Resistor")
      (fields (field (name "ALTIUM_VALUE") "10K 1%") (field (name "PUBLISHER") "Altium Limited"))
      (libsource (lib "Miscellaneous Devices") (part "Res1"))
    )
    (comp (ref "S1")
      (value "开关")
      (footprint "YT-8008-112A")
      (description "Single-Pole, Single-Throw Switch")
      (fields
        (field (name "ALTIUM_VALUE") "DC30V/1A YT-8008-112A")
        (field (name "PUBLISHER") "Altium Limited")
      )
      (libsource (lib "Miscellaneous Devices") (part "SW-SPST"))
    )
    (comp (ref "S2")
      (value "贴片轻触按钮")
      (footprint "Touch button")
      (description "Switch")
      (fields (field (name "ALTIUM_VALUE") "3.5*6*2.5mm") (field (name "PUBLISHER") "Altium Limited"))
      (libsource (lib "Miscellaneous Devices") (part "SW-PB"))
    )
    (comp (ref "S3")
      (value "开关")
      (footprint "DS-01")
      (description "Single-Pole, Single-Throw Switch")
      (fields (field (name "ALTIUM_VALUE") "DS-01") (field (name "PUBLISHER") "Altium Limited"))
      (libsource (lib "Miscellaneous Devices") (part "SW-SPST"))
    )
    (comp (ref "U1")
      (value "LS1C300B_176A")
      (footprint "QFP176")
      (description "龙芯1C300B QFP176A")
      (fields (field (name "ALTIUM_VALUE") "LS1C300B_176A"))
      (libsource (lib "LGHLIB") (part "LS1C300B_176A"))
    )
    (comp (ref "U2")
      (value "四通道单刀双掷模拟开关")
      (footprint "SOP-16")
      (description "四通道单刀双掷模拟开关 ，EN 低电平使能，IN 低电平 1#端导通，高电平2#端导通，DX是公共端")
      (fields (field (name "ALTIUM_VALUE") "CH440G"))
      (libsource (lib "LGHLIB") (part "CH440"))
    )
    (comp (ref "U3")
      (value "SDRAM")
      (footprint "TSOP54")
      (description "ISSI 公司SDRAM ， 166, 133, 100 MHz")
      (fields (field (name "ALTIUM_VALUE") "V54C3256164VHI6/IS42S16400-7T"))
      (libsource (lib "LGHLIB") (part "IS42S16400"))
    )
    (comp (ref "U4")
      (value "NOR FLASH")
      (footprint "SOIC-8-N")
      (description "nor flash W25Q64....华邦")
      (fields (field (name "ALTIUM_VALUE") "W25Q80"))
      (libsource (lib "LGHLIB") (part "W25Q80"))
    )
    (comp (ref "U5")
      (value "电源稳压芯片")
      (footprint "SOIC-8")
      (description "电源稳压芯片MPS,2A，18V的同步整流降压转换器")
      (fields (field (name "ALTIUM_VALUE") "MP1482DS"))
      (libsource (lib "LGHLIB") (part "MP1482"))
    )
    (comp (ref "U6")
      (value "通信芯片")
      (footprint "SOP28")
      (description "USB to Print Port / Parallel")
      (fields (field (name "ALTIUM_VALUE") "CH341A"))
      (libsource (lib "*") (part "CH341S_P"))
    )
    (comp (ref "U8")
      (value "电源稳压芯片")
      (footprint "SOIC-8")
      (description "电源稳压芯片MPS,2A，18V的同步整流降压转换器")
      (fields (field (name "ALTIUM_VALUE") "MP1482DS"))
      (libsource (lib "LGHLIB") (part "MP1482"))
    )
    (comp (ref "Y1")
      (value "直插晶振")
      (footprint "HC-49S")
      (description "Crystal Oscillator")
      (fields (field (name "ALTIUM_VALUE") "24MHz") (field (name "PUBLISHER") "Altium Limited"))
      (libsource (lib "Miscellaneous Devices") (part "XTAL"))
    )
    (comp (ref "Y2")
      (value "直插晶振")
      (footprint "TC-38")
      (description "Crystal Oscillator")
      (fields (field (name "ALTIUM_VALUE") "32.768KHz") (field (name "PUBLISHER") "Altium Limited"))
      (libsource (lib "Miscellaneous Devices") (part "XTAL"))
    )
    (comp (ref "Y3")
      (value "直插晶振")
      (footprint "HC-49S")
      (description "Crystal")
      (fields (field (name "ALTIUM_VALUE") "12MHz"))
      (libsource (lib "*") (part "CRYSTAL"))
    )
  )
  (nets
    (net (code "1") (name "/3") (class "Default")
      (node (ref "P1") (pin "3") (pinfunction "3_3") (pintype "passive"))
      (node (ref "U1") (pin "3") (pinfunction "LCD_CLK_/PIX_CLK/GPIO76_3") (pintype "passive"))
    )
    (net (code "2") (name "/4") (class "Default")
      (node (ref "P1") (pin "4") (pinfunction "4_4") (pintype "passive"))
      (node (ref "U1") (pin "4") (pinfunction "LCD_HSYNC_/GPIO74_/SPI0_CS1/__Sdio_Dat2__/UART0_RX_/PWM2_/I2C_SDA1_/SDRAM_CS1_4") (pintype "passive"))
    )
    (net (code "3") (name "/5") (class "Default")
      (node (ref "P1") (pin "5") (pinfunction "5_5") (pintype "passive"))
      (node (ref "U1") (pin "5") (pinfunction "LCD_VSYNC_/GPIO75_/SPI0_CS2/__Sdio_Dat3_/_UART0_TX_/PWM3_/I2C_SCL1_5") (pintype "passive"))
    )
    (net (code "4") (name "/6") (class "Default")
      (node (ref "P1") (pin "6") (pinfunction "6_6") (pintype "passive"))
      (node (ref "U1") (pin "6") (pinfunction "LCD_EN_/GPIO77_6") (pintype "passive"))
    )
    (net (code "5") (name "/7") (class "Default")
      (node (ref "P1") (pin "7") (pinfunction "7_7") (pintype "passive"))
      (node (ref "U1") (pin "7") (pinfunction "LCD_D0/LCD_B3/GPIO58_/UART4_RX/_UART0_CTS_7") (pintype "passive"))
    )
    (net (code "6") (name "/8") (class "Default")
      (node (ref "P1") (pin "8") (pinfunction "8_8") (pintype "passive"))
      (node (ref "U1") (pin "8") (pinfunction "LCD_D1/LCD_B4/GPIO59_/UART4_TX/_UART0_RTS_8") (pintype "passive"))
    )
    (net (code "7") (name "/9") (class "Default")
      (node (ref "P1") (pin "9") (pinfunction "9_9") (pintype "passive"))
      (node (ref "U1") (pin "9") (pinfunction "LCD_D2/LCD_B5/GPIO60_/UART5_RX/_UART0_DSR_9") (pintype "passive"))
    )
    (net (code "8") (name "/10") (class "Default")
      (node (ref "P1") (pin "10") (pinfunction "10_10") (pintype "passive"))
      (node (ref "U1") (pin "10") (pinfunction "LCD_D3/_LCD_B6_/GPIO61_/UART5_TX/_UART0_DTR_10") (pintype "passive"))
    )
    (net (code "9") (name "/12") (class "Default")
      (node (ref "P1") (pin "12") (pinfunction "12_12") (pintype "passive"))
      (node (ref "U1") (pin "12") (pinfunction "LCD_D4_/LCD_B7_/GPIO62_/UART6_RX/__UART0_DCD_12") (pintype "passive"))
    )
    (net (code "10") (name "/13") (class "Default")
      (node (ref "P1") (pin "13") (pinfunction "13_13") (pintype "passive"))
      (node (ref "U1") (pin "13") (pinfunction "LCD_D5_/LCD_G2_/GPIO63_/UART6_TX/UART0_RI_13") (pintype "passive"))
    )
    (net (code "11") (name "/14") (class "Default")
      (node (ref "P1") (pin "14") (pinfunction "14_14") (pintype "passive"))
      (node (ref "U1") (pin "14") (pinfunction "LCD_D6_/LCD_G3_/GPIO64_/UART7_RX_14") (pintype "passive"))
    )
    (net (code "12") (name "/15") (class "Default")
      (node (ref "P1") (pin "15") (pinfunction "15_15") (pintype "passive"))
      (node (ref "U1") (pin "15") (pinfunction "LCD_D7_/LCD_G4_/GPIO65_/UART7_TX_15") (pintype "passive"))
    )
    (net (code "13") (name "/16") (class "Default")
      (node (ref "P1") (pin "16") (pinfunction "16_16") (pintype "passive"))
      (node (ref "U1") (pin "16") (pinfunction "LCD_D8_/LCD_G5_/GPIO66_/UART8_RX_16") (pintype "passive"))
    )
    (net (code "14") (name "/17") (class "Default")
      (node (ref "P1") (pin "17") (pinfunction "17_17") (pintype "passive"))
      (node (ref "U1") (pin "17") (pinfunction "LCD_D9_/LCD_G6_/GPIO67_/UART8_TX_17") (pintype "passive"))
    )
    (net (code "15") (name "/19") (class "Default")
      (node (ref "P1") (pin "19") (pinfunction "19_19") (pintype "passive"))
      (node (ref "U1") (pin "19") (pinfunction "LCD_D10__/LCD_G7/_GPIO68_/UART9_RX/__UART8_CTS_19") (pintype "passive"))
    )
    (net (code "16") (name "/20") (class "Default")
      (node (ref "P1") (pin "20") (pinfunction "20_20") (pintype "passive"))
      (node (ref "U1") (pin "20") (pinfunction "LCD_R3__/LCD_D11_/GPIO69_/UART9_TX/__UART8_RTS_20") (pintype "passive"))
    )
    (net (code "17") (name "/21") (class "Default")
      (node (ref "P1") (pin "21") (pinfunction "21_21") (pintype "passive"))
      (node (ref "U1") (pin "21") (pinfunction "LCD_D12__/LCD_R4__/GPIO70_/UART10_RX/__UART8_DSR_21") (pintype "passive"))
    )
    (net (code "18") (name "/23") (class "Default")
      (node (ref "P1") (pin "22") (pinfunction "22_22") (pintype "passive"))
      (node (ref "U1") (pin "23") (pinfunction "LCD_D13_/LCD_R5__/GPIO71_/UART10_TX/__UART8_DTR_23") (pintype "passive"))
    )
    (net (code "19") (name "/24") (class "Default")
      (node (ref "P1") (pin "23") (pinfunction "23_23") (pintype "passive"))
      (node (ref "U1") (pin "24") (pinfunction "LCD_D14__/LCD_R6__/GPIO72_/UART11_RX/__UART8_DCD_24") (pintype "passive"))
    )
    (net (code "20") (name "/25") (class "Default")
      (node (ref "P1") (pin "24") (pinfunction "24_24") (pintype "passive"))
      (node (ref "U1") (pin "25") (pinfunction "LCD_D15__/LCD_R7__/GPIO73_/UART11_TX/__UART8_RI_25") (pintype "passive"))
    )
    (net (code "21") (name "/70") (class "Default")
      (node (ref "P4") (pin "2") (pinfunction "2_2") (pintype "passive"))
      (node (ref "U1") (pin "70") (pinfunction "I2S_DI_/GPIO87_/UART7_RX_70") (pintype "passive"))
    )
    (net (code "22") (name "/71") (class "Default")
      (node (ref "P4") (pin "3") (pinfunction "3_3") (pintype "passive"))
      (node (ref "U1") (pin "71") (pinfunction "I2S_DO_/GPIO88_/UART7_TX_71") (pintype "passive"))
    )
    (net (code "23") (name "/72") (class "Default")
      (node (ref "P4") (pin "4") (pinfunction "4_4") (pintype "passive"))
      (node (ref "U1") (pin "72") (pinfunction "I2S_LRCK_/GPIO89_/UART8_RX_72") (pintype "passive"))
    )
    (net (code "24") (name "/73") (class "Default")
      (node (ref "P4") (pin "5") (pinfunction "5_5") (pintype "passive"))
      (node (ref "U1") (pin "73") (pinfunction "I2S_BCLK_/GPIO90_/UART8_TX_73") (pintype "passive"))
    )
    (net (code "25") (name "/74") (class "Default")
      (node (ref "P4") (pin "6") (pinfunction "6_6") (pintype "passive"))
      (node (ref "U1") (pin "74") (pinfunction "I2C_SDA0_/GPIO85_/UART9_RX/__UART8_CTS_74") (pintype "passive"))
    )
    (net (code "26") (name "/75") (class "Default")
      (node (ref "P4") (pin "7") (pinfunction "7_7") (pintype "passive"))
      (node (ref "U1") (pin "75") (pinfunction "I2C_SCL0__/GPIO86_/UART9_TX/__UART8_RTS_75") (pintype "passive"))
    )
    (net (code "27") (name "/76") (class "Default")
      (node (ref "P4") (pin "8") (pinfunction "8_8") (pintype "passive"))
      (node (ref "U1") (pin "76") (pinfunction "I2S_MCLK_/GPIO91_76") (pintype "passive"))
    )
    (net (code "28") (name "/77") (class "Default")
      (node (ref "P4") (pin "9") (pinfunction "9_9") (pintype "passive"))
      (node (ref "U1") (pin "77") (pinfunction "PWM1_/GPIO92_/ADC_YN_77") (pintype "passive"))
    )
    (net (code "29") (name "/78") (class "Default")
      (node (ref "P4") (pin "10") (pinfunction "10_10") (pintype "passive"))
      (node (ref "U1") (pin "78") (pinfunction "PWM0/__CAMCLKOUT__/GPIO06_/ADC_XN_78") (pintype "passive"))
    )
    (net (code "30") (name "/79") (class "Default")
      (node (ref "P4") (pin "11") (pinfunction "11_11") (pintype "passive"))
      (node (ref "U1") (pin "79") (pinfunction "SPI0_CS2_/GPIO83_/Sdio_Dat3_79") (pintype "passive"))
    )
    (net (code "31") (name "/82") (class "Default")
      (node (ref "P4") (pin "14") (pinfunction "14_14") (pintype "passive"))
      (node (ref "U1") (pin "82") (pinfunction "ADC_VREF_82") (pintype "passive"))
    )
    (net (code "32") (name "/85") (class "Default")
      (node (ref "P4") (pin "15") (pinfunction "15_15") (pintype "passive"))
      (node (ref "U1") (pin "85") (pinfunction "ADC_D0_85") (pintype "passive"))
    )
    (net (code "33") (name "/86") (class "Default")
      (node (ref "P4") (pin "16") (pinfunction "16_16") (pintype "passive"))
      (node (ref "U1") (pin "86") (pinfunction "ADC_D1_86") (pintype "passive"))
    )
    (net (code "34") (name "/87") (class "Default")
      (node (ref "P4") (pin "17") (pinfunction "17_17") (pintype "passive"))
      (node (ref "U1") (pin "87") (pinfunction "ADC_XP_87") (pintype "passive"))
    )
    (net (code "35") (name "/88") (class "Default")
      (node (ref "P4") (pin "18") (pinfunction "18_18") (pintype "passive"))
      (node (ref "U1") (pin "88") (pinfunction "ADC_YP_88") (pintype "passive"))
    )
    (net (code "36") (name "/89") (class "Default")
      (node (ref "P4") (pin "19") (pinfunction "19_19") (pintype "passive"))
      (node (ref "U1") (pin "89") (pinfunction "SPI0_CS3_/GPIO84_/CAMCLKOUT_/UART10_RX/__UART8_DSR_89") (pintype "passive"))
    )
    (net (code "37") (name "/93") (class "Default")
      (node (ref "P4") (pin "20") (pinfunction "20_20") (pintype "passive"))
      (node (ref "U1") (pin "93") (pinfunction "SPI0_CS1_/GPIO82_/Sdio_Dat2_/UART10_TX/__UART8_DTR_93") (pintype "passive"))
    )
    (net (code "38") (name "/103") (class "Default")
      (node (ref "P4") (pin "23") (pinfunction "23_23") (pintype "passive"))
      (node (ref "U1") (pin "103") (pinfunction "CAMDATA7_/GPIO57_/LCD_R2_/CAN1_TX_/I2C_SCL2_/UART7_RX_103") (pintype "passive"))
    )
    (net (code "39") (name "/104") (class "Default")
      (node (ref "P4") (pin "24") (pinfunction "24_24") (pintype "passive"))
      (node (ref "U1") (pin "104") (pinfunction "CAMDATA6_/GPIO56_/LCD_R1_/CAN1_RX_/I2C_SDA2_/UART7_TX_104") (pintype "passive"))
    )
    (net (code "40") (name "/105") (class "Default")
      (node (ref "P4") (pin "25") (pinfunction "25_25") (pintype "passive"))
      (node (ref "U1") (pin "105") (pinfunction "CAMDATA5_/GPIO55_/LCD_R0_/CAN0_TX_/I2C_SCL1_/UART8_RX_105") (pintype "passive"))
    )
    (net (code "41") (name "/106") (class "Default")
      (node (ref "P4") (pin "26") (pinfunction "26_26") (pintype "passive"))
      (node (ref "U1") (pin "106") (pinfunction "CAMDATA4_/GPIO54_/LCD_G1_/CAN0_RX_/I2C_SDA1_/UART8_TX_106") (pintype "passive"))
    )
    (net (code "42") (name "/107") (class "Default")
      (node (ref "P4") (pin "27") (pinfunction "27_27") (pintype "passive"))
      (node (ref "U1") (pin "107") (pinfunction "CAMDATA3_/GPIO53_/LCD_G0_/CAMCLKOUT_/PWM3_/UART9_RX/__UART8_CTS_107") (pintype "passive"))
    )
    (net (code "43") (name "/108") (class "Default")
      (node (ref "P4") (pin "28") (pinfunction "28_28") (pintype "passive"))
      (node (ref "U1") (pin "108") (pinfunction "CAMDATA2_/GPIO52_/LCD_B2_/SPI1_CS3_/PWM2_/UART9_TX/__UART8_RTS_108") (pintype "passive"))
    )
    (net (code "44") (name "/109") (class "Default")
      (node (ref "P6") (pin "13") (pinfunction "13_13") (pintype "passive"))
      (node (ref "U1") (pin "109") (pinfunction "CAMDATA1_/GPIO51_/LCD_B1_/SPI1_CS2_/I2C_SCL2_/UART10_RX/__UART8_DSR_109") (pintype "passive"))
    )
    (net (code "45") (name "/110") (class "Default")
      (node (ref "P6") (pin "14") (pinfunction "14_14") (pintype "passive"))
      (node (ref "U1") (pin "110") (pinfunction "CAMDATA0_/GPIO50_/LCD_B0_/SPI1_CS1_/I2C_SDA2_/UART10_TX/__UART8_DTR_110") (pintype "passive"))
    )
    (net (code "46") (name "/112") (class "Default")
      (node (ref "P6") (pin "12") (pinfunction "12_12") (pintype "passive"))
      (node (ref "U1") (pin "112") (pinfunction "CAMHSYNC_/GPIO49_/NAND_RDY3_/SPI1_CS0_/I2C_SCL1_/UART11_RX/__UART8_DCD_112") (pintype "passive"))
    )
    (net (code "47") (name "/113") (class "Default")
      (node (ref "P6") (pin "9") (pinfunction "9_9") (pintype "passive"))
      (node (ref "U1") (pin "113") (pinfunction "CAMVSYNC_/GPIO48_/NAND_CE#3_/SPI1_MOSI_/I2C_SDA1_/UART11_TX/__UART8_RI_113") (pintype "passive"))
    )
    (net (code "48") (name "/114") (class "Default")
      (node (ref "P6") (pin "10") (pinfunction "10_10") (pintype "passive"))
      (node (ref "U1") (pin "114") (pinfunction "CAMCLKOUT_/GPIO47_/SRAM_A25_/NAND_RDY2_/SPI1_MISO_/PWM3_/UART6_RX/__UART0_DCD_114") (pintype "passive"))
    )
    (net (code "49") (name "/115") (class "Default")
      (node (ref "P6") (pin "7") (pinfunction "7_7") (pintype "passive"))
      (node (ref "U1") (pin "115") (pinfunction "CAMPCLKIN_/GPIO46_/SRAM_A24_/NAND_CE#2_/SPI1_CLK_/PWM2_/UART6_TX/__UART0_RI_115") (pintype "passive"))
    )
    (net (code "50") (name "/116") (class "Default")
      (node (ref "P6") (pin "8") (pinfunction "8_8") (pintype "passive"))
      (node (ref "U1") (pin "116") (pinfunction "NAND_7_/GPIO20_/SPI1_CS1/__Sdio_Dat2__/MAC_MDIO_/CAMDATA0_/I2C_SCL2_116") (pintype "passive"))
    )
    (net (code "51") (name "/117") (class "Default")
      (node (ref "P6") (pin "5") (pinfunction "5_5") (pintype "passive"))
      (node (ref "U1") (pin "117") (pinfunction "NAND_6_/GPIO19_/SPI1_CS2/__Sdio_Dat3__/MAC_MDC_/CAMDATA1_/I2C_SDA2_117") (pintype "passive"))
    )
    (net (code "52") (name "/118(5)") (class "Default")
      (node (ref "P6") (pin "6") (pinfunction "6_6") (pintype "passive"))
      (node (ref "R16") (pin "2") (pinfunction "2_2") (pintype "passive"))
      (node (ref "U1") (pin "118") (pinfunction "NAND_5_/GPIO18_/UART1_TX_/UART3_TX_/CAMDATA2_/PWM2_118") (pintype "passive"))
    )
    (net (code "53") (name "/119(4)") (class "Default")
      (node (ref "P6") (pin "3") (pinfunction "3_3") (pintype "passive"))
      (node (ref "R15") (pin "2") (pinfunction "2_2") (pintype "passive"))
      (node (ref "U1") (pin "119") (pinfunction "NAND_4_/GPIO17_/UART1_RX_/UART3_RX_/CAMDATA3_/PWM3_119") (pintype "passive"))
    )
    (net (code "54") (name "/120") (class "Default")
      (node (ref "P6") (pin "4") (pinfunction "4_4") (pintype "passive"))
      (node (ref "U1") (pin "120") (pinfunction "NAND_3_/GPIO16_/SPI1_CS0/__Sdio_Dat1__/CAN1_TX_/CAMDATA4_/I2S_LRCK_120") (pintype "passive"))
    )
    (net (code "55") (name "/121") (class "Default")
      (node (ref "P6") (pin "1") (pinfunction "1_1") (pintype "passive"))
      (node (ref "U1") (pin "121") (pinfunction "NAND_2_/GPIO15_/SPI1_MOSI/__Sdio_Dat0/CAN1_RX_/CAMDATA5_/I2S_DO_121") (pintype "passive"))
    )
    (net (code "56") (name "/122") (class "Default")
      (node (ref "P6") (pin "2") (pinfunction "2_2") (pintype "passive"))
      (node (ref "U1") (pin "122") (pinfunction "NAND_1_/GPIO14_/SPI1_MISO/__Sdio_Cmd__/CAN0_TX_/CAMDATA6_/I2S_BCLK_122") (pintype "passive"))
    )
    (net (code "57") (name "/123") (class "Default")
      (node (ref "P3") (pin "13") (pinfunction "13_13") (pintype "passive"))
      (node (ref "U1") (pin "123") (pinfunction "NAND_0_/GPIO13_/SPI1_CLK/__Sdio_clk__/CAN0_RX_/CAMDATA7_/I2S_MCLK_/GPIO_123") (pintype "passive"))
    )
    (net (code "58") (name "/127") (class "Default")
      (node (ref "P3") (pin "9") (pinfunction "9_9") (pintype "passive"))
      (node (ref "U1") (pin "127") (pinfunction "NAND_RDY_/GPIO07_127") (pintype "passive"))
    )
    (net (code "59") (name "/128") (class "Default")
      (node (ref "P3") (pin "10") (pinfunction "10_10") (pintype "passive"))
      (node (ref "U1") (pin "128") (pinfunction "NAND_CLE_/GPIO08_/GPIO_128") (pintype "passive"))
    )
    (net (code "60") (name "/129") (class "Default")
      (node (ref "P3") (pin "7") (pinfunction "7_7") (pintype "passive"))
      (node (ref "U1") (pin "129") (pinfunction "NAND_ALE_/GPIO09_/GPIO_129") (pintype "passive"))
    )
    (net (code "61") (name "/130") (class "Default")
      (node (ref "P3") (pin "8") (pinfunction "8_8") (pintype "passive"))
      (node (ref "U1") (pin "130") (pinfunction "NAND_RD#_/GPIO10_/GPIO_130") (pintype "passive"))
    )
    (net (code "62") (name "/132") (class "Default")
      (node (ref "P3") (pin "6") (pinfunction "6_6") (pintype "passive"))
      (node (ref "U1") (pin "132") (pinfunction "NAND_CE#_/GPIO11_/GPIO_132") (pintype "passive"))
    )
    (net (code "63") (name "/133") (class "Default")
      (node (ref "P3") (pin "3") (pinfunction "3_3") (pintype "passive"))
      (node (ref "U1") (pin "133") (pinfunction "NAND_WR#_/GPIO12_/GPIO_133") (pintype "passive"))
    )
    (net (code "64") (name "/134") (class "Default")
      (node (ref "P3") (pin "4") (pinfunction "4_4") (pintype "passive"))
      (node (ref "U1") (pin "134") (pinfunction "MAC_TXEN_/GPIO21_/I2S_MCLK_/NAND_CLE_/I2C_SDA2_/CAN0_RX_/UART8_RX_134") (pintype "passive"))
    )
    (net (code "65") (name "/135") (class "Default")
      (node (ref "P3") (pin "1") (pinfunction "1_1") (pintype "passive"))
      (node (ref "U1") (pin "135") (pinfunction "MAC_TXD0_/GPIO23_/I2S_DO_/NAND_ALE_/UART0_RX_/CAN1_RX_/UART4_RX/__UART0_CTS_135") (pintype "passive"))
    )
    (net (code "66") (name "/136") (class "Default")
      (node (ref "P3") (pin "2") (pinfunction "2_2") (pintype "passive"))
      (node (ref "U1") (pin "136") (pinfunction "MAC_TXD1_/GPIO24_/I2S_LRCK_/NAND_WR#_/UART0_TX_/CAN1_TX_/UART4_TX/__UART0_RTS_136") (pintype "passive"))
    )
    (net (code "67") (name "/137") (class "Default")
      (node (ref "P2") (pin "27") (pinfunction "27_27") (pintype "passive"))
      (node (ref "U1") (pin "137") (pinfunction "MAC_RXER_/GPIO25_/I2S_DI_/NAND_RDY0_/I2C_SDA1_/CAMCLKOUT_/UART5_RX/__UART0_DSR_137") (pintype "passive"))
    )
    (net (code "68") (name "/138") (class "Default")
      (node (ref "P2") (pin "28") (pinfunction "28_28") (pintype "passive"))
      (node (ref "U1") (pin "138") (pinfunction "MAC_RXDV_/GPIO26_/SPI1_CS3_/NAND_CE#0_/I2C_SCL1_/CAMPCLKIN_/UART5_TX/__UART0_DTR__/GPIO_138") (pintype "passive"))
    )
    (net (code "69") (name "/139") (class "Default")
      (node (ref "P2") (pin "25") (pinfunction "25_25") (pintype "passive"))
      (node (ref "U1") (pin "139") (pinfunction "MAC_RXD0_/GPIO27_/I2C_SDA_/PWM2_/UART2_RX_/CAMVSYNC_/UART6_RX/__UART0_DCD__/GPIO_139") (pintype "passive"))
    )
    (net (code "70") (name "/140") (class "Default")
      (node (ref "P2") (pin "26") (pinfunction "26_26") (pintype "passive"))
      (node (ref "U1") (pin "140") (pinfunction "MAC_RXD1_/GPIO28_/I2C_SCL_/PWM3_/UART2_TX_/CAMHSYNC_/UART6_TX/__UART0_RI__/GPIO_140") (pintype "passive"))
    )
    (net (code "71") (name "/141") (class "Default")
      (node (ref "P2") (pin "23") (pinfunction "23_23") (pintype "passive"))
      (node (ref "U1") (pin "141") (pinfunction "MAC_MDC_/GPIO29_/CAMDATA7_/NAND_CE#1_/PWM2_/I2C_SCL1_/UART8_TX_/GPIO_141") (pintype "passive"))
    )
    (net (code "72") (name "/143") (class "Default")
      (node (ref "P2") (pin "21") (pinfunction "21_21") (pintype "passive"))
      (node (ref "U1") (pin "143") (pinfunction "MAC_MDIO_/GPIO30_/CAMDATA6_/NAND_RDY1_/LCD_B0_/I2C_SDA1_/GPIO_143") (pintype "passive"))
    )
    (net (code "73") (name "/144") (class "Default")
      (node (ref "P2") (pin "22") (pinfunction "22_22") (pintype "passive"))
      (node (ref "U1") (pin "144") (pinfunction "MAC_RXD2_/GPIO31_/CAMDATA5_/NAND_CS#2_/LCD_B1_/CAN1_RX_/UART11_RX/__UART8_DCD__/GPIO_144") (pintype "passive"))
    )
    (net (code "74") (name "/145") (class "Default")
      (node (ref "D3") (pin "2") (pinfunction "K_2") (pintype "passive"))
      (node (ref "P2") (pin "19") (pinfunction "19_19") (pintype "passive"))
      (node (ref "U1") (pin "145") (pinfunction "MAC_TXD2_/GPIO32_/CAMDATA4_/NAND_RDY2_/LCD_B2_/CAN1_TX_/UART11_TX/__UART8_RI_145") (pintype "passive"))
    )
    (net (code "75") (name "/146") (class "Default")
      (node (ref "P2") (pin "20") (pinfunction "20_20") (pintype "passive"))
      (node (ref "U1") (pin "146") (pinfunction "MAC_RXD3_/GPIO33_/CAMDATA3_/UART3_RX_/LCD_G0_/SPI1_CLK/__Sdio_clk_146") (pintype "passive"))
    )
    (net (code "76") (name "/147") (class "Default")
      (node (ref "P2") (pin "17") (pinfunction "17_17") (pintype "passive"))
      (node (ref "U1") (pin "147") (pinfunction "MAC_TXD3_/GPIO34_/CAMDATA2_/UART3_TX_/LCD_G1_/SPI1_MISO/__Sdio_Cmd_147") (pintype "passive"))
    )
    (net (code "77") (name "/148") (class "Default")
      (node (ref "P2") (pin "18") (pinfunction "18_18") (pintype "passive"))
      (node (ref "U1") (pin "148") (pinfunction "MAC_TXC_/GPIO22_/I2S_BCLK_/NAND_RD#_/I2C_SCL2_/CANO_TX_/SDRAM_CS1_148") (pintype "passive"))
    )
    (net (code "78") (name "/151") (class "Default")
      (node (ref "P2") (pin "13") (pinfunction "13_13") (pintype "passive"))
      (node (ref "U1") (pin "151") (pinfunction "MAC_CRS__(ONLY_MII)_/GPIO35_/CAMDATA1_/PWM1_/LCD_R0_/SPI1_MOSI/__Sdio_Dat0_151") (pintype "passive"))
    )
    (net (code "79") (name "/157") (class "Default")
      (node (ref "P2") (pin "11") (pinfunction "11_11") (pintype "passive"))
      (node (ref "U1") (pin "157") (pinfunction "OTG_DM_157") (pintype "passive"))
    )
    (net (code "80") (name "/158") (class "Default")
      (node (ref "P2") (pin "10") (pinfunction "10_10") (pintype "passive"))
      (node (ref "U1") (pin "158") (pinfunction "OTG_DP_158") (pintype "passive"))
    )
    (net (code "81") (name "/160") (class "Default")
      (node (ref "P2") (pin "8") (pinfunction "8_8") (pintype "passive"))
      (node (ref "U1") (pin "160") (pinfunction "OTG_VBUS_160") (pintype "passive"))
    )
    (net (code "82") (name "/161") (class "Default")
      (node (ref "P2") (pin "7") (pinfunction "7_7") (pintype "passive"))
      (node (ref "U1") (pin "161") (pinfunction "OTG_ID_161") (pintype "passive"))
    )
    (net (code "83") (name "/168") (class "Default")
      (node (ref "P2") (pin "6") (pinfunction "6_6") (pintype "passive"))
      (node (ref "U1") (pin "168") (pinfunction "USB_DM_168") (pintype "passive"))
    )
    (net (code "84") (name "/169") (class "Default")
      (node (ref "P2") (pin "3") (pinfunction "3_3") (pintype "passive"))
      (node (ref "U1") (pin "169") (pinfunction "USB_DP_169") (pintype "passive"))
    )
    (net (code "85") (name "/CH_CLK_SPI0_CLK") (class "Default")
      (node (ref "U2") (pin "2") (pinfunction "S1A_2") (pintype "passive"))
      (node (ref "U6") (pin "18") (pinfunction "D3_18") (pintype "bidirectional"))
    )
    (net (code "86") (name "/CH_MISO_SPI0_MISO") (class "Default")
      (node (ref "U2") (pin "11") (pinfunction "S1C_11") (pintype "passive"))
      (node (ref "U6") (pin "22") (pinfunction "D7_22") (pintype "bidirectional"))
    )
    (net (code "87") (name "/CH_MOSI_SPI0_MOSI") (class "Default")
      (node (ref "U2") (pin "5") (pinfunction "S1B_5") (pintype "passive"))
      (node (ref "U6") (pin "20") (pinfunction "D5_20") (pintype "bidirectional"))
    )
    (net (code "88") (name "/CH_SDA") (class "Default")
      (node (ref "R42") (pin "1") (pinfunction "1_1") (pintype "passive"))
      (node (ref "S3") (pin "2") (pinfunction "NO_2") (pintype "passive"))
      (node (ref "U2") (pin "1") (pinfunction "IN_1") (pintype "passive"))
      (node (ref "U6") (pin "23") (pinfunction "SDA_23") (pintype "bidirectional"))
    )
    (net (code "89") (name "/D+") (class "Default")
      (node (ref "P8") (pin "A6") (pinfunction "DP1_A6") (pintype "passive"))
      (node (ref "P8") (pin "B6") (pinfunction "DP2_B6") (pintype "passive"))
      (node (ref "U6") (pin "10") (pinfunction "UD+_10") (pintype "bidirectional"))
    )
    (net (code "90") (name "/D-") (class "Default")
      (node (ref "P8") (pin "A7") (pinfunction "DN1_A7") (pintype "passive"))
      (node (ref "P8") (pin "B7") (pinfunction "DN2_B7") (pintype "passive"))
      (node (ref "U6") (pin "11") (pinfunction "UD-_11") (pintype "bidirectional"))
    )
    (net (code "91") (name "/EJTAG_RST") (class "Default")
      (node (ref "P5") (pin "1") (pinfunction "TRST_N_1") (pintype "passive"))
      (node (ref "R35") (pin "1") (pinfunction "1_1") (pintype "passive"))
      (node (ref "U1") (pin "100") (pinfunction "EJTAG_RST_/GPIO05_/CAMDATA0_/I2C_SCL2_/PWM1_/UART2_TX_/GPIO_100") (pintype "passive"))
    )
    (net (code "92") (name "/EJTAG_SEL") (class "Default")
      (node (ref "R38") (pin "1") (pinfunction "1_1") (pintype "passive"))
      (node (ref "R39") (pin "1") (pinfunction "1_1") (pintype "passive"))
      (node (ref "U1") (pin "95") (pinfunction "EJTAG_SEL_/GPIO00_/CAMCLKOUT_/I2C_SDA0_/CAN0_RX_/UART3_RX_/SDRAM_CS1_/GPIO_95") (pintype "passive"))
    )
    (net (code "93") (name "/EJTAG_TCK") (class "Default")
      (node (ref "P5") (pin "5") (pinfunction "TCK_5") (pintype "passive"))
      (node (ref "R30") (pin "1") (pinfunction "1_1") (pintype "passive"))
      (node (ref "U1") (pin "96") (pinfunction "EJTAG_TCK_/GPIO01_/CAMPCLKIN_/I2C_SCL0_/CAN0_TX_/UART3_TX_/GPIO_96") (pintype "passive"))
    )
    (net (code "94") (name "/EJTAG_TDI") (class "Default")
      (node (ref "P5") (pin "2") (pinfunction "TDI_2") (pintype "passive"))
      (node (ref "R33") (pin "1") (pinfunction "1_1") (pintype "passive"))
      (node (ref "R34") (pin "1") (pinfunction "1_1") (pintype "passive"))
      (node (ref "U1") (pin "99") (pinfunction "EJTAG_TDI_/GPIO02_/CAMVSYNC_/I2C_SDA1_/CAN1_RX_/UART1_RX_/GPIO_99") (pintype "passive"))
    )
    (net (code "95") (name "/EJTAG_TDO") (class "Default")
      (node (ref "P5") (pin "3") (pinfunction "TDO_3") (pintype "passive"))
      (node (ref "R32") (pin "1") (pinfunction "1_1") (pintype "passive"))
      (node (ref "U1") (pin "98") (pinfunction "EJTAG_TDO_/GPIO03_/CAMHSYNC_/I2C_SCL1_/CAN1_TX_/UART1_TX_/GPIO_98") (pintype "passive"))
    )
    (net (code "96") (name "/EJTAG_TMS") (class "Default")
      (node (ref "P5") (pin "4") (pinfunction "TMS_4") (pintype "passive"))
      (node (ref "R31") (pin "1") (pinfunction "1_1") (pintype "passive"))
      (node (ref "U1") (pin "97") (pinfunction "EJTAG_TMS_/GPIO04_/CAMDATA1_/I2C_SDA2_/PWM0_/UART2_RX_/GPIO_97") (pintype "passive"))
    )
    (net (code "97") (name "/FLASH_CS0") (class "Default")
      (node (ref "R6") (pin "2") (pinfunction "2_2") (pintype "passive"))
      (node (ref "U2") (pin "12") (pinfunction "DD_12") (pintype "passive"))
      (node (ref "U4") (pin "1") (pinfunction "~{CS}_1") (pintype "passive"))
    )
    (net (code "98") (name "/JTAG_SEL") (class "Default")
      (node (ref "P5") (pin "7") (pinfunction "NC_7") (pintype "passive"))
      (node (ref "R36") (pin "1") (pinfunction "1_1") (pintype "passive"))
      (node (ref "R37") (pin "1") (pinfunction "1_1") (pintype "passive"))
      (node (ref "U1") (pin "126") (pinfunction "JTAG_SEL_/SDRAM_CS1_/UART6_TX/__UART0_RI_126") (pintype "passive"))
    )
    (net (code "99") (name "/RTCI") (class "Default")
      (node (ref "C3") (pin "2") (pinfunction "2_2") (pintype "passive"))
      (node (ref "R41") (pin "2") (pinfunction "2_2") (pintype "passive"))
      (node (ref "U1") (pin "175") (pinfunction "RTC_CLK_I_175") (pintype "passive"))
      (node (ref "Y2") (pin "2") (pinfunction "OSC2_2") (pintype "passive"))
    )
    (net (code "100") (name "/RTCO") (class "Default")
      (node (ref "C4") (pin "2") (pinfunction "2_2") (pintype "passive"))
      (node (ref "R41") (pin "1") (pinfunction "1_1") (pintype "passive"))
      (node (ref "U1") (pin "174") (pinfunction "RTC_CLK_O_174") (pintype "passive"))
      (node (ref "Y2") (pin "1") (pinfunction "OSC1_1") (pintype "passive"))
    )
    (net (code "101") (name "/RTC_VDDA") (class "Default")
      (node (ref "D1") (pin "2") (pinfunction "K_2") (pintype "passive"))
      (node (ref "P2") (pin "4") (pinfunction "4_4") (pintype "passive"))
      (node (ref "U1") (pin "176") (pinfunction "RTC_VR_VDDA_176") (pintype "passive"))
    )
    (net (code "102") (name "/SDRAM_A0") (class "Default")
      (node (ref "U1") (pin "67") (pinfunction "SD_A00/__SRAM_A00_67") (pintype "passive"))
      (node (ref "U3") (pin "23") (pinfunction "A0_23") (pintype "passive"))
    )
    (net (code "103") (name "/SDRAM_A1") (class "Default")
      (node (ref "U1") (pin "66") (pinfunction "SD_A01/__SRAM_A01_66") (pintype "passive"))
      (node (ref "U3") (pin "24") (pinfunction "A1_24") (pintype "passive"))
    )
    (net (code "104") (name "/SDRAM_A2") (class "Default")
      (node (ref "U1") (pin "65") (pinfunction "SD_A02/__SRAM_A02_65") (pintype "passive"))
      (node (ref "U3") (pin "25") (pinfunction "A2_25") (pintype "passive"))
    )
    (net (code "105") (name "/SDRAM_A3") (class "Default")
      (node (ref "U1") (pin "64") (pinfunction "SD_A03/__SRAM_A03_64") (pintype "passive"))
      (node (ref "U3") (pin "26") (pinfunction "A3_26") (pintype "passive"))
    )
    (net (code "106") (name "/SDRAM_A4") (class "Default")
      (node (ref "U1") (pin "63") (pinfunction "SD_A04/__SRAM_A04_63") (pintype "passive"))
      (node (ref "U3") (pin "29") (pinfunction "A4_29") (pintype "passive"))
    )
    (net (code "107") (name "/SDRAM_A5") (class "Default")
      (node (ref "U1") (pin "62") (pinfunction "SD_A05/__SRAM_A05_62") (pintype "passive"))
      (node (ref "U3") (pin "30") (pinfunction "A5_30") (pintype "passive"))
    )
    (net (code "108") (name "/SDRAM_A6") (class "Default")
      (node (ref "U1") (pin "61") (pinfunction "SD_A06/__SRAM_A06_61") (pintype "passive"))
      (node (ref "U3") (pin "31") (pinfunction "A6_31") (pintype "passive"))
    )
    (net (code "109") (name "/SDRAM_A7") (class "Default")
      (node (ref "U1") (pin "60") (pinfunction "SD_A07/__SRAM_A07_60") (pintype "passive"))
      (node (ref "U3") (pin "32") (pinfunction "A7_32") (pintype "passive"))
    )
    (net (code "110") (name "/SDRAM_A8") (class "Default")
      (node (ref "U1") (pin "59") (pinfunction "SD_A08/__SRAM_A08_59") (pintype "passive"))
      (node (ref "U3") (pin "33") (pinfunction "A8_33") (pintype "passive"))
    )
    (net (code "111") (name "/SDRAM_A9") (class "Default")
      (node (ref "U1") (pin "58") (pinfunction "SD_A09/__SRAM_A09_58") (pintype "passive"))
      (node (ref "U3") (pin "34") (pinfunction "A9_34") (pintype "passive"))
    )
    (net (code "112") (name "/SDRAM_A10") (class "Default")
      (node (ref "U1") (pin "57") (pinfunction "SD_A10/__SRAM_A10_57") (pintype "passive"))
      (node (ref "U3") (pin "22") (pinfunction "A10_22") (pintype "passive"))
    )
    (net (code "113") (name "/SDRAM_A11") (class "Default")
      (node (ref "U1") (pin "56") (pinfunction "SD_A11/__SRAM_A11_56") (pintype "passive"))
      (node (ref "U3") (pin "35") (pinfunction "A11_35") (pintype "passive"))
    )
    (net (code "114") (name "/SDRAM_A12") (class "Default")
      (node (ref "U1") (pin "55") (pinfunction "SD_A12/__SRAM_A12_55") (pintype "passive"))
      (node (ref "U3") (pin "36") (pinfunction "NC_36") (pintype "passive"))
    )
    (net (code "115") (name "/SDRAM_BA0") (class "Default")
      (node (ref "U1") (pin "52") (pinfunction "SD_BA0/__SRAM_A17_52") (pintype "passive"))
      (node (ref "U3") (pin "20") (pinfunction "BA0_20") (pintype "passive"))
    )
    (net (code "116") (name "/SDRAM_BA1") (class "Default")
      (node (ref "U1") (pin "50") (pinfunction "SD_BA1/__SRAM_A16_50") (pintype "passive"))
      (node (ref "U3") (pin "21") (pinfunction "BA1_21") (pintype "passive"))
    )
    (net (code "117") (name "/SDRAM_CKE") (class "Default")
      (node (ref "U1") (pin "53") (pinfunction "SD_CKE/__SRAM_A13_53") (pintype "passive"))
      (node (ref "U3") (pin "37") (pinfunction "CKE_37") (pintype "passive"))
    )
    (net (code "118") (name "/SDRAM_CLK") (class "Default")
      (node (ref "U1") (pin "54") (pinfunction "SD_CLK/__SRAM_OEn_54") (pintype "passive"))
      (node (ref "U3") (pin "38") (pinfunction "CLK_38") (pintype "passive"))
    )
    (net (code "119") (name "/SDRAM_D0") (class "Default")
      (node (ref "U1") (pin "44") (pinfunction "SD_D00/__SRAM_D00_44") (pintype "passive"))
      (node (ref "U3") (pin "2") (pinfunction "I/O0_2") (pintype "passive"))
    )
    (net (code "120") (name "/SDRAM_D1") (class "Default")
      (node (ref "U1") (pin "43") (pinfunction "SD_D01/__SRAM_D01_43") (pintype "passive"))
      (node (ref "U3") (pin "4") (pinfunction "I/O1_4") (pintype "passive"))
    )
    (net (code "121") (name "/SDRAM_D2") (class "Default")
      (node (ref "U1") (pin "42") (pinfunction "SD_D02/__SRAM_D02_42") (pintype "passive"))
      (node (ref "U3") (pin "5") (pinfunction "I/O2_5") (pintype "passive"))
    )
    (net (code "122") (name "/SDRAM_D3") (class "Default")
      (node (ref "U1") (pin "41") (pinfunction "SD_D03/__SRAM_D03_41") (pintype "passive"))
      (node (ref "U3") (pin "7") (pinfunction "I/O3_7") (pintype "passive"))
    )
    (net (code "123") (name "/SDRAM_D4") (class "Default")
      (node (ref "U1") (pin "40") (pinfunction "SD_D04/__SRAM_D04_40") (pintype "passive"))
      (node (ref "U3") (pin "8") (pinfunction "I/O4_8") (pintype "passive"))
    )
    (net (code "124") (name "/SDRAM_D5") (class "Default")
      (node (ref "U1") (pin "39") (pinfunction "SD_D05/__SRAM_D05_39") (pintype "passive"))
      (node (ref "U3") (pin "10") (pinfunction "I/O5_10") (pintype "passive"))
    )
    (net (code "125") (name "/SDRAM_D6") (class "Default")
      (node (ref "U1") (pin "38") (pinfunction "SD_D06/__SRAM_D06_38") (pintype "passive"))
      (node (ref "U3") (pin "11") (pinfunction "I/O6_11") (pintype "passive"))
    )
    (net (code "126") (name "/SDRAM_D7") (class "Default")
      (node (ref "U1") (pin "37") (pinfunction "SD_D07/__SRAM_D07_37") (pintype "passive"))
      (node (ref "U3") (pin "13") (pinfunction "I/O7_13") (pintype "passive"))
    )
    (net (code "127") (name "/SDRAM_D8") (class "Default")
      (node (ref "U1") (pin "34") (pinfunction "SD_D08/__SRAM_D08_/GPIO97_/I2S_MCLK_/NAND_CLE_/I2C_SDA2_/CAN0_RX_34") (pintype "passive"))
      (node (ref "U3") (pin "42") (pinfunction "I/O8_42") (pintype "passive"))
    )
    (net (code "128") (name "/SDRAM_D9") (class "Default")
      (node (ref "U1") (pin "33") (pinfunction "SD_D09/__SRAM_D09_/GPIO98_/I2S_BCLK_/NAND_RD#_/I2C_SCL2_/CANO_TX_33") (pintype "passive"))
      (node (ref "U3") (pin "44") (pinfunction "I/O9_44") (pintype "passive"))
    )
    (net (code "129") (name "/SDRAM_D10") (class "Default")
      (node (ref "U1") (pin "32") (pinfunction "SD_D10/__SRAM_D10__/GPIO99_/I2S_DI_/NAND_ALE_/UART0_RX_/CAN1_RX_32") (pintype "passive"))
      (node (ref "U3") (pin "45") (pinfunction "I/O10_45") (pintype "passive"))
    )
    (net (code "130") (name "/SDRAM_D11") (class "Default")
      (node (ref "U1") (pin "31") (pinfunction "SD_D11/__SRAM_D11__/GPIO100_/I2S_LRCK_/NAND_WR#_/UART0_TX_/CAN1_TX_31") (pintype "passive"))
      (node (ref "U3") (pin "47") (pinfunction "I/O11_47") (pintype "passive"))
    )
    (net (code "131") (name "/SDRAM_D12") (class "Default")
      (node (ref "U1") (pin "30") (pinfunction "SD_D12/__SRAM_D13/_GPIO101_/UART1_RX_/NAND_RDY_/I2C_SDA1_/PWM0_30") (pintype "passive"))
      (node (ref "U3") (pin "48") (pinfunction "I/O12_48") (pintype "passive"))
    )
    (net (code "132") (name "/SDRAM_D13") (class "Default")
      (node (ref "U1") (pin "29") (pinfunction "SD_D13/__SRAM_D13__/GPIO102_/UART1_TX_/NAND_CE#_/I2C_SCL1_/PWM1_29") (pintype "passive"))
      (node (ref "U3") (pin "50") (pinfunction "I/O13_50") (pintype "passive"))
    )
    (net (code "133") (name "/SDRAM_D14") (class "Default")
      (node (ref "U1") (pin "28") (pinfunction "SD_D14/__SRAM_D14__/GPIO103_/I2C_SDA/_PWM2_/UART2_RX_/MDC_28") (pintype "passive"))
      (node (ref "U3") (pin "51") (pinfunction "I/O14_51") (pintype "passive"))
    )
    (net (code "134") (name "/SDRAM_D15") (class "Default")
      (node (ref "U1") (pin "27") (pinfunction "SD_D15/__SRAM_D15_/GPIO104_/I2C_SCL_/PWM3_/UART2_TX_/MDIO_27") (pintype "passive"))
      (node (ref "U3") (pin "53") (pinfunction "I/O15_53") (pintype "passive"))
    )
    (net (code "135") (name "/SDRAM_DQM0") (class "Default")
      (node (ref "U1") (pin "36") (pinfunction "SD_DQM0/__SRAM_BLEn_36") (pintype "passive"))
      (node (ref "U3") (pin "15") (pinfunction "LDQM_15") (pintype "passive"))
    )
    (net (code "136") (name "/SDRAM_DQM1") (class "Default")
      (node (ref "U1") (pin "35") (pinfunction "SD_DQM1/__SRAM_BHEn__/GPIO96_/I2S_DO_/PWM1_/XTALI_/UART6_RX/__UART0_DCD_35") (pintype "passive"))
      (node (ref "U3") (pin "39") (pinfunction "UDQM_39") (pintype "passive"))
    )
    (net (code "137") (name "/SPI0_CLK") (class "Default")
      (node (ref "R17") (pin "1") (pinfunction "1_1") (pintype "passive"))
      (node (ref "U1") (pin "94") (pinfunction "SPI_CLK_/GPIO78_/Sdio_clk_/UART5_TX/__UART0_DTR_94") (pintype "passive"))
      (node (ref "U2") (pin "3") (pinfunction "S2A_3") (pintype "passive"))
    )
    (net (code "138") (name "/SPI0_CS0") (class "Default")
      (node (ref "U1") (pin "92") (pinfunction "SPI0_CS0_/GPIO81_/Sdio_Dat1_/SDRAM_CS1_/UART5_RX/__UART0_DSR_92") (pintype "passive"))
      (node (ref "U2") (pin "13") (pinfunction "S2D_13") (pintype "passive"))
    )
    (net (code "139") (name "/SPI0_MISO") (class "Default")
      (node (ref "R19") (pin "1") (pinfunction "1_1") (pintype "passive"))
      (node (ref "U1") (pin "90") (pinfunction "SPI0_MISO_/GPIO80_/Sdio_Cmd_/UART4_RX/__UART0_CTS_90") (pintype "passive"))
      (node (ref "U2") (pin "10") (pinfunction "S2C_10") (pintype "passive"))
    )
    (net (code "140") (name "/SPI0_MOSI") (class "Default")
      (node (ref "R18") (pin "1") (pinfunction "1_1") (pintype "passive"))
      (node (ref "U1") (pin "91") (pinfunction "SPI0_MOSI_/GPIO79_/Sdio_Dat0_/UART4_TX/__UART0_RTS_91") (pintype "passive"))
      (node (ref "U2") (pin "6") (pinfunction "S2B_6") (pintype "passive"))
    )
    (net (code "141") (name "/UART2_RX") (class "Default")
      (node (ref "P2") (pin "15") (pinfunction "15_15") (pintype "passive"))
      (node (ref "U1") (pin "149") (pinfunction "MAC_COL_/GPIO36_/CAMDATA0_/UART2_RX_/LCD_R1_/SPI1_CS0/__Sdio_Dat1_149") (pintype "passive"))
      (node (ref "U6") (pin "5") (pinfunction "ERR#_5") (pintype "passive"))
    )
    (net (code "142") (name "/UART2_TX") (class "Default")
      (node (ref "P2") (pin "16") (pinfunction "16_16") (pintype "passive"))
      (node (ref "U1") (pin "150") (pinfunction "MAC_RXC_/GPIO37_/PWM3_/UART2_TX_/LCD_R2_/SPI1_CS1/__Sdio_Dat2_150") (pintype "passive"))
      (node (ref "U6") (pin "6") (pinfunction "PEMP_6") (pintype "passive"))
    )
    (net (code "143") (name "/W_CLK") (class "Default")
      (node (ref "U2") (pin "4") (pinfunction "DA_4") (pintype "passive"))
      (node (ref "U4") (pin "6") (pinfunction "CLK_6") (pintype "passive"))
    )
    (net (code "144") (name "/W_MISO") (class "Default")
      (node (ref "U2") (pin "9") (pinfunction "DC_9") (pintype "passive"))
      (node (ref "U4") (pin "2") (pinfunction "MISO_2") (pintype "passive"))
    )
    (net (code "145") (name "/W_MOSI") (class "Default")
      (node (ref "U2") (pin "7") (pinfunction "DB_7") (pintype "passive"))
      (node (ref "U4") (pin "5") (pinfunction "MOSI_5") (pintype "passive"))
    )
    (net (code "146") (name "/XTALI") (class "Default")
      (node (ref "C1") (pin "2") (pinfunction "2_2") (pintype "passive"))
      (node (ref "R40") (pin "2") (pinfunction "2_2") (pintype "passive"))
      (node (ref "U1") (pin "1") (pinfunction "XTALI_1") (pintype "passive"))
      (node (ref "Y1") (pin "1") (pinfunction "OSC1_1") (pintype "passive"))
    )
    (net (code "147") (name "/XTALO") (class "Default")
      (node (ref "C2") (pin "2") (pinfunction "2_2") (pintype "passive"))
      (node (ref "R40") (pin "1") (pinfunction "1_1") (pintype "passive"))
      (node (ref "U1") (pin "2") (pinfunction "XTAL0_2") (pintype "passive"))
      (node (ref "Y1") (pin "2") (pinfunction "OSC2_2") (pintype "passive"))
    )
    (net (code "148") (name "/~{CH_CS}") (class "Default")
      (node (ref "U2") (pin "14") (pinfunction "S1D_14") (pintype "passive"))
      (node (ref "U6") (pin "15") (pinfunction "D0_15") (pintype "bidirectional"))
    )
    (net (code "149") (name "/~{SDRAM_CAS}") (class "Default")
      (node (ref "R23") (pin "2") (pinfunction "2_2") (pintype "passive"))
      (node (ref "U1") (pin "47") (pinfunction "SD_CASn/__SRAM_A15_47") (pintype "passive"))
      (node (ref "U3") (pin "17") (pinfunction "~{CAS}_17") (pintype "passive"))
    )
    (net (code "150") (name "/~{SDRAM_CS}") (class "Default")
      (node (ref "R21") (pin "2") (pinfunction "2_2") (pintype "passive"))
      (node (ref "U1") (pin "49") (pinfunction "SD_CSn/__SRAM_CSn_49") (pintype "passive"))
      (node (ref "U3") (pin "19") (pinfunction "~{CS}_19") (pintype "passive"))
    )
    (net (code "151") (name "/~{SDRAM_RAS}") (class "Default")
      (node (ref "R22") (pin "2") (pinfunction "2_2") (pintype "passive"))
      (node (ref "U1") (pin "48") (pinfunction "SD_RASn/__SRAM_A14_48") (pintype "passive"))
      (node (ref "U3") (pin "18") (pinfunction "~{RAS}_18") (pintype "passive"))
    )
    (net (code "152") (name "/~{SDRAM_WE}") (class "Default")
      (node (ref "R24") (pin "2") (pinfunction "2_2") (pintype "passive"))
      (node (ref "U1") (pin "46") (pinfunction "SD_WEn/__SRAM_WEn_46") (pintype "passive"))
      (node (ref "U3") (pin "16") (pinfunction "~{WE}_16") (pintype "passive"))
    )
    (net (code "153") (name "/~{SPI_HOLD}") (class "Default")
      (node (ref "R5") (pin "2") (pinfunction "2_2") (pintype "passive"))
      (node (ref "U4") (pin "7") (pinfunction "~{HOLD}_7") (pintype "passive"))
    )
    (net (code "154") (name "/~{SPI_WP}") (class "Default")
      (node (ref "R7") (pin "2") (pinfunction "2_2") (pintype "passive"))
      (node (ref "U4") (pin "3") (pinfunction "~{WP}_3") (pintype "passive"))
    )
    (net (code "155") (name "/~{SYS_RESET}") (class "Default")
      (node (ref "C32") (pin "2") (pinfunction "2_2") (pintype "passive"))
      (node (ref "P3") (pin "11") (pinfunction "11_11") (pintype "passive"))
      (node (ref "R9") (pin "1") (pinfunction "1_1") (pintype "passive"))
      (node (ref "S2") (pin "2") (pinfunction "2_2") (pintype "passive"))
      (node (ref "U1") (pin "125") (pinfunction "~{SYS_RST}_125") (pintype "passive"))
    )
    (net (code "156") (name "1V2") (class "Default")
      (node (ref "C20") (pin "2") (pinfunction "2_2") (pintype "passive"))
      (node (ref "C21") (pin "2") (pinfunction "2_2") (pintype "passive"))
      (node (ref "C22") (pin "2") (pinfunction "2_2") (pintype "passive"))
      (node (ref "C23") (pin "2") (pinfunction "2_2") (pintype "passive"))
      (node (ref "C24") (pin "2") (pinfunction "2_2") (pintype "passive"))
      (node (ref "C25") (pin "2") (pinfunction "2_2") (pintype "passive"))
      (node (ref "C26") (pin "2") (pinfunction "2_2") (pintype "passive"))
      (node (ref "C27") (pin "2") (pinfunction "2_2") (pintype "passive"))
      (node (ref "C28") (pin "2") (pinfunction "2_2") (pintype "passive"))
      (node (ref "C29") (pin "2") (pinfunction "2_2") (pintype "passive"))
      (node (ref "C30") (pin "2") (pinfunction "2_2") (pintype "passive"))
      (node (ref "C31") (pin "2") (pinfunction "2_2") (pintype "passive"))
      (node (ref "C60") (pin "1") (pinfunction "1_1") (pintype "passive"))
      (node (ref "C61") (pin "1") (pinfunction "1_1") (pintype "passive"))
      (node (ref "C62") (pin "2") (pinfunction "2_2") (pintype "passive"))
      (node (ref "L2") (pin "1") (pinfunction "1_1") (pintype "passive"))
      (node (ref "R13") (pin "2") (pinfunction "2_2") (pintype "passive"))
      (node (ref "U1") (pin "101") (pinfunction "CORE_VDD_101") (pintype "passive"))
      (node (ref "U1") (pin "11") (pinfunction "CORE_VDD_11") (pintype "passive"))
      (node (ref "U1") (pin "124") (pinfunction "CORE_VDD_124") (pintype "passive"))
      (node (ref "U1") (pin "152") (pinfunction "CORE_VDD_152") (pintype "passive"))
      (node (ref "U1") (pin "154") (pinfunction "OTG_DVDD_154") (pintype "passive"))
      (node (ref "U1") (pin "164") (pinfunction "USB_DVDD_164") (pintype "passive"))
      (node (ref "U1") (pin "171") (pinfunction "PLL_VDD12_171") (pintype "passive"))
      (node (ref "U1") (pin "26") (pinfunction "CORE_VDD_26") (pintype "passive"))
      (node (ref "U1") (pin "68") (pinfunction "CORE_VDD_68") (pintype "passive"))
    )
    (net (code "157") (name "3V3") (class "Default")
      (node (ref "C10") (pin "2") (pinfunction "2_2") (pintype "passive"))
      (node (ref "C11") (pin "2") (pinfunction "2_2") (pintype "passive"))
      (node (ref "C12") (pin "2") (pinfunction "2_2") (pintype "passive"))
      (node (ref "C13") (pin "2") (pinfunction "2_2") (pintype "passive"))
      (node (ref "C14") (pin "2") (pinfunction "2_2") (pintype "passive"))
      (node (ref "C15") (pin "2") (pinfunction "2_2") (pintype "passive"))
      (node (ref "C16") (pin "2") (pinfunction "2_2") (pintype "passive"))
      (node (ref "C17") (pin "2") (pinfunction "2_2") (pintype "passive"))
      (node (ref "C37") (pin "2") (pinfunction "2_2") (pintype "passive"))
      (node (ref "C38") (pin "2") (pinfunction "2_2") (pintype "passive"))
      (node (ref "C39") (pin "2") (pinfunction "2_2") (pintype "passive"))
      (node (ref "C40") (pin "2") (pinfunction "2_2") (pintype "passive"))
      (node (ref "C41") (pin "2") (pinfunction "2_2") (pintype "passive"))
      (node (ref "C42") (pin "2") (pinfunction "2_2") (pintype "passive"))
      (node (ref "C43") (pin "2") (pinfunction "2_2") (pintype "passive"))
      (node (ref "C44") (pin "2") (pinfunction "2_2") (pintype "passive"))
      (node (ref "C45") (pin "2") (pinfunction "2_2") (pintype "passive"))
      (node (ref "C46") (pin "2") (pinfunction "2_2") (pintype "passive"))
      (node (ref "C47") (pin "2") (pinfunction "2_2") (pintype "passive"))
      (node (ref "C48") (pin "2") (pinfunction "2_2") (pintype "passive"))
      (node (ref "C5") (pin "2") (pinfunction "2_2") (pintype "passive"))
      (node (ref "C52") (pin "2") (pinfunction "2_2") (pintype "passive"))
      (node (ref "C56") (pin "2") (pinfunction "2_2") (pintype "passive"))
      (node (ref "C57") (pin "2") (pinfunction "2_2") (pintype "passive"))
      (node (ref "C58") (pin "2") (pinfunction "2_2") (pintype "passive"))
      (node (ref "C59") (pin "2") (pinfunction "2_2") (pintype "passive"))
      (node (ref "C6") (pin "2") (pinfunction "2_2") (pintype "passive"))
      (node (ref "C67") (pin "1") (pinfunction "1_1") (pintype "passive"))
      (node (ref "C68") (pin "1") (pinfunction "1_1") (pintype "passive"))
      (node (ref "C69") (pin "2") (pinfunction "2_2") (pintype "passive"))
      (node (ref "C7") (pin "2") (pinfunction "2_2") (pintype "passive"))
      (node (ref "C70") (pin "2") (pinfunction "2_2") (pintype "passive"))
      (node (ref "C71") (pin "2") (pinfunction "2_2") (pintype "passive"))
      (node (ref "C8") (pin "2") (pinfunction "2_2") (pintype "passive"))
      (node (ref "C9") (pin "2") (pinfunction "2_2") (pintype "passive"))
      (node (ref "D1") (pin "1") (pinfunction "A_1") (pintype "passive"))
      (node (ref "L1") (pin "1") (pinfunction "1_1") (pintype "passive"))
      (node (ref "L3") (pin "1") (pinfunction "1_1") (pintype "passive"))
      (node (ref "P1") (pin "27") (pinfunction "27_27") (pintype "passive"))
      (node (ref "P1") (pin "28") (pinfunction "28_28") (pintype "passive"))
      (node (ref "P5") (pin "8") (pinfunction "3V3_8") (pintype "passive"))
      (node (ref "R1") (pin "2") (pinfunction "2_2") (pintype "passive"))
      (node (ref "R15") (pin "1") (pinfunction "1_1") (pintype "passive"))
      (node (ref "R17") (pin "2") (pinfunction "2_2") (pintype "passive"))
      (node (ref "R18") (pin "2") (pinfunction "2_2") (pintype "passive"))
      (node (ref "R19") (pin "2") (pinfunction "2_2") (pintype "passive"))
      (node (ref "R21") (pin "1") (pinfunction "1_1") (pintype "passive"))
      (node (ref "R22") (pin "1") (pinfunction "1_1") (pintype "passive"))
      (node (ref "R23") (pin "1") (pinfunction "1_1") (pintype "passive"))
      (node (ref "R24") (pin "1") (pinfunction "1_1") (pintype "passive"))
      (node (ref "R28") (pin "2") (pinfunction "2_2") (pintype "passive"))
      (node (ref "R3") (pin "2") (pinfunction "2_2") (pintype "passive"))
      (node (ref "R30") (pin "2") (pinfunction "2_2") (pintype "passive"))
      (node (ref "R31") (pin "2") (pinfunction "2_2") (pintype "passive"))
      (node (ref "R32") (pin "2") (pinfunction "2_2") (pintype "passive"))
      (node (ref "R33") (pin "2") (pinfunction "2_2") (pintype "passive"))
      (node (ref "R36") (pin "2") (pinfunction "2_2") (pintype "passive"))
      (node (ref "R38") (pin "2") (pinfunction "2_2") (pintype "passive"))
      (node (ref "R42") (pin "2") (pinfunction "2_2") (pintype "passive"))
      (node (ref "R5") (pin "1") (pinfunction "1_1") (pintype "passive"))
      (node (ref "R6") (pin "1") (pinfunction "1_1") (pintype "passive"))
      (node (ref "R7") (pin "1") (pinfunction "1_1") (pintype "passive"))
      (node (ref "R9") (pin "2") (pinfunction "2_2") (pintype "passive"))
      (node (ref "U1") (pin "102") (pinfunction "IO_VDD_102") (pintype "passive"))
      (node (ref "U1") (pin "131") (pinfunction "IO_VDD_131") (pintype "passive"))
      (node (ref "U1") (pin "155") (pinfunction "OTG_VDD33_155") (pintype "passive"))
      (node (ref "U1") (pin "165") (pinfunction "USB_VDD33_165") (pintype "passive"))
      (node (ref "U1") (pin "173") (pinfunction "PLL_VDD33_173") (pintype "passive"))
      (node (ref "U1") (pin "18") (pinfunction "IO_VDD_18") (pintype "passive"))
      (node (ref "U1") (pin "45") (pinfunction "IO_VDD_45") (pintype "passive"))
      (node (ref "U1") (pin "69") (pinfunction "IO_VDD_69") (pintype "passive"))
      (node (ref "U2") (pin "16") (pinfunction "VCC_16") (pintype "passive"))
      (node (ref "U3") (pin "1") (pinfunction "VCC_1") (pintype "passive"))
      (node (ref "U3") (pin "14") (pinfunction "VCC_14") (pintype "passive"))
      (node (ref "U3") (pin "27") (pinfunction "VCC_27") (pintype "passive"))
      (node (ref "U3") (pin "3") (pinfunction "VCCQ_3") (pintype "passive"))
      (node (ref "U3") (pin "43") (pinfunction "VCCQ_43") (pintype "passive"))
      (node (ref "U3") (pin "49") (pinfunction "VCCQ_49") (pintype "passive"))
      (node (ref "U3") (pin "9") (pinfunction "VCCQ_9") (pintype "passive"))
      (node (ref "U4") (pin "8") (pinfunction "VCC_8") (pintype "passive"))
      (node (ref "U6") (pin "28") (pinfunction "VCC_28") (pintype "power_in"))
      (node (ref "U6") (pin "9") (pinfunction "V3_9") (pintype "power_in"))
    )
    (net (code "158") (name "5V") (class "Default")
      (node (ref "C36") (pin "1") (pinfunction "1_1") (pintype "passive"))
      (node (ref "C53") (pin "1") (pinfunction "1_1") (pintype "passive"))
      (node (ref "C54") (pin "2") (pinfunction "2_2") (pintype "passive"))
      (node (ref "C65") (pin "2") (pinfunction "2_2") (pintype "passive"))
      (node (ref "F1") (pin "1") (pinfunction "1_1") (pintype "passive"))
      (node (ref "R10") (pin "1") (pinfunction "1_1") (pintype "passive"))
      (node (ref "R25") (pin "1") (pinfunction "1_1") (pintype "passive"))
      (node (ref "U5") (pin "2") (pinfunction "IN_2") (pintype "passive"))
      (node (ref "U8") (pin "2") (pinfunction "IN_2") (pintype "passive"))
    )
    (net (code "159") (name "5V1") (class "Default")
      (node (ref "P1") (pin "1") (pinfunction "1_1") (pintype "passive"))
      (node (ref "P2") (pin "1") (pinfunction "1_1") (pintype "passive"))
      (node (ref "P8") (pin "A4") (pinfunction "VBUS_A4") (pintype "passive"))
      (node (ref "P8") (pin "A9") (pinfunction "VBUS_A9") (pintype "passive"))
      (node (ref "P8") (pin "B4") (pinfunction "VBUS_B4") (pintype "passive"))
      (node (ref "P8") (pin "B9") (pinfunction "VBUS_B9") (pintype "passive"))
      (node (ref "S1") (pin "2") (pinfunction "NO_2") (pintype "passive"))
    )
    (net (code "160") (name "ADC_VDDA") (class "Default")
      (node (ref "C18") (pin "2") (pinfunction "2_2") (pintype "passive"))
      (node (ref "C19") (pin "2") (pinfunction "2_2") (pintype "passive"))
      (node (ref "L1") (pin "2") (pinfunction "2_2") (pintype "passive"))
      (node (ref "U1") (pin "83") (pinfunction "ADC_VDDA_83") (pintype "passive"))
    )
    (net (code "161") (name "GND") (class "Default")
      (node (ref "C1") (pin "1") (pinfunction "1_1") (pintype "passive"))
      (node (ref "C10") (pin "1") (pinfunction "1_1") (pintype "passive"))
      (node (ref "C11") (pin "1") (pinfunction "1_1") (pintype "passive"))
      (node (ref "C12") (pin "1") (pinfunction "1_1") (pintype "passive"))
      (node (ref "C13") (pin "1") (pinfunction "1_1") (pintype "passive"))
      (node (ref "C14") (pin "1") (pinfunction "1_1") (pintype "passive"))
      (node (ref "C15") (pin "1") (pinfunction "1_1") (pintype "passive"))
      (node (ref "C16") (pin "1") (pinfunction "1_1") (pintype "passive"))
      (node (ref "C17") (pin "1") (pinfunction "1_1") (pintype "passive"))
      (node (ref "C18") (pin "1") (pinfunction "1_1") (pintype "passive"))
      (node (ref "C19") (pin "1") (pinfunction "1_1") (pintype "passive"))
      (node (ref "C2") (pin "1") (pinfunction "1_1") (pintype "passive"))
      (node (ref "C20") (pin "1") (pinfunction "1_1") (pintype "passive"))
      (node (ref "C21") (pin "1") (pinfunction "1_1") (pintype "passive"))
      (node (ref "C22") (pin "1") (pinfunction "1_1") (pintype "passive"))
      (node (ref "C23") (pin "1") (pinfunction "1_1") (pintype "passive"))
      (node (ref "C24") (pin "1") (pinfunction "1_1") (pintype "passive"))
      (node (ref "C25") (pin "1") (pinfunction "1_1") (pintype "passive"))
      (node (ref "C26") (pin "1") (pinfunction "1_1") (pintype "passive"))
      (node (ref "C27") (pin "1") (pinfunction "1_1") (pintype "passive"))
      (node (ref "C28") (pin "1") (pinfunction "1_1") (pintype "passive"))
      (node (ref "C29") (pin "1") (pinfunction "1_1") (pintype "passive"))
      (node (ref "C3") (pin "1") (pinfunction "1_1") (pintype "passive"))
      (node (ref "C30") (pin "1") (pinfunction "1_1") (pintype "passive"))
      (node (ref "C31") (pin "1") (pinfunction "1_1") (pintype "passive"))
      (node (ref "C32") (pin "1") (pinfunction "1_1") (pintype "passive"))
      (node (ref "C33") (pin "2") (pinfunction "2_2") (pintype "passive"))
      (node (ref "C36") (pin "2") (pinfunction "2_2") (pintype "passive"))
      (node (ref "C37") (pin "1") (pinfunction "1_1") (pintype "passive"))
      (node (ref "C38") (pin "1") (pinfunction "1_1") (pintype "passive"))
      (node (ref "C39") (pin "1") (pinfunction "1_1") (pintype "passive"))
      (node (ref "C4") (pin "1") (pinfunction "1_1") (pintype "passive"))
      (node (ref "C40") (pin "1") (pinfunction "1_1") (pintype "passive"))
      (node (ref "C41") (pin "1") (pinfunction "1_1") (pintype "passive"))
      (node (ref "C42") (pin "1") (pinfunction "1_1") (pintype "passive"))
      (node (ref "C43") (pin "1") (pinfunction "1_1") (pintype "passive"))
      (node (ref "C44") (pin "1") (pinfunction "1_1") (pintype "passive"))
      (node (ref "C45") (pin "1") (pinfunction "1_1") (pintype "passive"))
      (node (ref "C46") (pin "1") (pinfunction "1_1") (pintype "passive"))
      (node (ref "C47") (pin "1") (pinfunction "1_1") (pintype "passive"))
      (node (ref "C48") (pin "1") (pinfunction "1_1") (pintype "passive"))
      (node (ref "C49") (pin "2") (pinfunction "2_2") (pintype "passive"))
      (node (ref "C5") (pin "1") (pinfunction "1_1") (pintype "passive"))
      (node (ref "C53") (pin "2") (pinfunction "2_2") (pintype "passive"))
      (node (ref "C54") (pin "1") (pinfunction "1_1") (pintype "passive"))
      (node (ref "C56") (pin "1") (pinfunction "1_1") (pintype "passive"))
      (node (ref "C57") (pin "1") (pinfunction "1_1") (pintype "passive"))
      (node (ref "C58") (pin "1") (pinfunction "1_1") (pintype "passive"))
      (node (ref "C59") (pin "1") (pinfunction "1_1") (pintype "passive"))
      (node (ref "C6") (pin "1") (pinfunction "1_1") (pintype "passive"))
      (node (ref "C60") (pin "2") (pinfunction "2_2") (pintype "passive"))
      (node (ref "C61") (pin "2") (pinfunction "2_2") (pintype "passive"))
      (node (ref "C62") (pin "1") (pinfunction "1_1") (pintype "passive"))
      (node (ref "C63") (pin "1") (pinfunction "1_1") (pintype "passive"))
      (node (ref "C64") (pin "1") (pinfunction "1_1") (pintype "passive"))
      (node (ref "C65") (pin "1") (pinfunction "1_1") (pintype "passive"))
      (node (ref "C67") (pin "2") (pinfunction "2_2") (pintype "passive"))
      (node (ref "C68") (pin "2") (pinfunction "2_2") (pintype "passive"))
      (node (ref "C69") (pin "1") (pinfunction "1_1") (pintype "passive"))
      (node (ref "C7") (pin "1") (pinfunction "1_1") (pintype "passive"))
      (node (ref "C70") (pin "1") (pinfunction "1_1") (pintype "passive"))
      (node (ref "C71") (pin "1") (pinfunction "1_1") (pintype "passive"))
      (node (ref "C8") (pin "1") (pinfunction "1_1") (pintype "passive"))
      (node (ref "C9") (pin "1") (pinfunction "1_1") (pintype "passive"))
      (node (ref "D2") (pin "1") (pinfunction "A_1") (pintype "passive"))
      (node (ref "D4") (pin "1") (pinfunction "A_1") (pintype "passive"))
      (node (ref "D5") (pin "2") (pinfunction "K_2") (pintype "passive"))
      (node (ref "P1") (pin "11") (pinfunction "11_11") (pintype "passive"))
      (node (ref "P1") (pin "18") (pinfunction "18_18") (pintype "passive"))
      (node (ref "P1") (pin "2") (pinfunction "2_2") (pintype "passive"))
      (node (ref "P1") (pin "25") (pinfunction "25_25") (pintype "passive"))
      (node (ref "P1") (pin "26") (pinfunction "26_26") (pintype "passive"))
      (node (ref "P2") (pin "12") (pinfunction "12_12") (pintype "passive"))
      (node (ref "P2") (pin "14") (pinfunction "14_14") (pintype "passive"))
      (node (ref "P2") (pin "2") (pinfunction "2_2") (pintype "passive"))
      (node (ref "P2") (pin "24") (pinfunction "24_24") (pintype "passive"))
      (node (ref "P2") (pin "5") (pinfunction "5_5") (pintype "passive"))
      (node (ref "P2") (pin "9") (pinfunction "9_9") (pintype "passive"))
      (node (ref "P3") (pin "12") (pinfunction "12_12") (pintype "passive"))
      (node (ref "P3") (pin "14") (pinfunction "14_14") (pintype "passive"))
      (node (ref "P3") (pin "5") (pinfunction "5_5") (pintype "passive"))
      (node (ref "P4") (pin "1") (pinfunction "1_1") (pintype "passive"))
      (node (ref "P4") (pin "12") (pinfunction "12_12") (pintype "passive"))
      (node (ref "P4") (pin "13") (pinfunction "13_13") (pintype "passive"))
      (node (ref "P4") (pin "21") (pinfunction "21_21") (pintype "passive"))
      (node (ref "P4") (pin "22") (pinfunction "22_22") (pintype "passive"))
      (node (ref "P5") (pin "10") (pinfunction "GND_10") (pintype "passive"))
      (node (ref "P5") (pin "11") (pinfunction "GND_11") (pintype "passive"))
      (node (ref "P5") (pin "12") (pinfunction "GND_12") (pintype "passive"))
      (node (ref "P5") (pin "13") (pinfunction "GND_13") (pintype "passive"))
      (node (ref "P5") (pin "14") (pinfunction "GND_14") (pintype "passive"))
      (node (ref "P6") (pin "11") (pinfunction "11_11") (pintype "passive"))
      (node (ref "P8") (pin "1") (pinfunction "GND_1") (pintype "passive"))
      (node (ref "P8") (pin "2") (pinfunction "GND_2") (pintype "passive"))
      (node (ref "P8") (pin "3") (pinfunction "GND_3") (pintype "passive"))
      (node (ref "P8") (pin "4") (pinfunction "GND_4") (pintype "passive"))
      (node (ref "P8") (pin "A1") (pinfunction "GND_A1") (pintype "passive"))
      (node (ref "P8") (pin "A12") (pinfunction "GND_A12") (pintype "passive"))
      (node (ref "P8") (pin "B1") (pinfunction "GND_B1") (pintype "passive"))
      (node (ref "P8") (pin "B12") (pinfunction "GND_B12") (pintype "passive"))
      (node (ref "R11") (pin "1") (pinfunction "1_1") (pintype "passive"))
      (node (ref "R12") (pin "2") (pinfunction "2_2") (pintype "passive"))
      (node (ref "R14") (pin "1") (pinfunction "1_1") (pintype "passive"))
      (node (ref "R16") (pin "1") (pinfunction "1_1") (pintype "passive"))
      (node (ref "R2") (pin "1") (pinfunction "1_1") (pintype "passive"))
      (node (ref "R20") (pin "1") (pinfunction "1_1") (pintype "passive"))
      (node (ref "R26") (pin "1") (pinfunction "1_1") (pintype "passive"))
      (node (ref "R27") (pin "2") (pinfunction "2_2") (pintype "passive"))
      (node (ref "R29") (pin "1") (pinfunction "1_1") (pintype "passive"))
      (node (ref "R34") (pin "2") (pinfunction "2_2") (pintype "passive"))
      (node (ref "R35") (pin "2") (pinfunction "2_2") (pintype "passive"))
      (node (ref "R37") (pin "2") (pinfunction "2_2") (pintype "passive"))
      (node (ref "R39") (pin "2") (pinfunction "2_2") (pintype "passive"))
      (node (ref "R4") (pin "1") (pinfunction "1_1") (pintype "passive"))
      (node (ref "R8") (pin "2") (pinfunction "2_2") (pintype "passive"))
      (node (ref "S2") (pin "1") (pinfunction "1_1") (pintype "passive"))
      (node (ref "S3") (pin "1") (pinfunction "COMMON_1") (pintype "passive"))
      (node (ref "U1") (pin "111") (pinfunction "CORE_VSS_111") (pintype "passive"))
      (node (ref "U1") (pin "142") (pinfunction "CORE_VSS_142") (pintype "passive"))
      (node (ref "U1") (pin "153") (pinfunction "OTG_DVSS_153") (pintype "passive"))
      (node (ref "U1") (pin "156") (pinfunction "OTG_VSS33_156") (pintype "passive"))
      (node (ref "U1") (pin "162") (pinfunction "CORE_VSS_162") (pintype "passive"))
      (node (ref "U1") (pin "163") (pinfunction "USB_DVSS_163") (pintype "passive"))
      (node (ref "U1") (pin "166") (pinfunction "USB_VSS33_166") (pintype "passive"))
      (node (ref "U1") (pin "170") (pinfunction "PLL_VSS12_170") (pintype "passive"))
      (node (ref "U1") (pin "172") (pinfunction "PLL_VSS33_172") (pintype "passive"))
      (node (ref "U1") (pin "22") (pinfunction "CORE_VSS_22") (pintype "passive"))
      (node (ref "U1") (pin "51") (pinfunction "CORE_VSS_51") (pintype "passive"))
      (node (ref "U1") (pin "80") (pinfunction "CORE_VSS_80") (pintype "passive"))
      (node (ref "U1") (pin "84") (pinfunction "ADC_VSSA_84") (pintype "passive"))
      (node (ref "U2") (pin "15") (pinfunction "~{EN}_15") (pintype "passive"))
      (node (ref "U2") (pin "8") (pinfunction "GND_8") (pintype "passive"))
      (node (ref "U3") (pin "12") (pinfunction "GNDQ_12") (pintype "passive"))
      (node (ref "U3") (pin "28") (pinfunction "GND_28") (pintype "passive"))
      (node (ref "U3") (pin "41") (pinfunction "GND_41") (pintype "passive"))
      (node (ref "U3") (pin "46") (pinfunction "GNDQ_46") (pintype "passive"))
      (node (ref "U3") (pin "52") (pinfunction "GNDQ_52") (pintype "passive"))
      (node (ref "U3") (pin "54") (pinfunction "GND_54") (pintype "passive"))
      (node (ref "U3") (pin "6") (pinfunction "GNDQ_6") (pintype "passive"))
      (node (ref "U4") (pin "4") (pinfunction "GND_4") (pintype "passive"))
      (node (ref "U5") (pin "4") (pinfunction "GND_4") (pintype "passive"))
      (node (ref "U6") (pin "12") (pinfunction "GND_12") (pintype "power_in"))
      (node (ref "U6") (pin "27") (pinfunction "BUSY_27") (pintype "input"))
      (node (ref "U8") (pin "4") (pinfunction "GND_4") (pintype "passive"))
    )
    (net (code "162") (name "Net-(C35-Pad1)") (class "Default")
      (node (ref "C35") (pin "1") (pinfunction "1_1") (pintype "passive"))
      (node (ref "R26") (pin "2") (pinfunction "2_2") (pintype "passive"))
    )
    (net (code "163") (name "Net-(C51-Pad1)") (class "Default")
      (node (ref "C51") (pin "1") (pinfunction "1_1") (pintype "passive"))
      (node (ref "R11") (pin "2") (pinfunction "2_2") (pintype "passive"))
    )
    (net (code "164") (name "Net-(C55-Pad1)") (class "Default")
      (node (ref "C55") (pin "1") (pinfunction "1_1") (pintype "passive"))
      (node (ref "R12") (pin "1") (pinfunction "1_1") (pintype "passive"))
    )
    (net (code "165") (name "Net-(C66-Pad1)") (class "Default")
      (node (ref "C66") (pin "1") (pinfunction "1_1") (pintype "passive"))
      (node (ref "R27") (pin "1") (pinfunction "1_1") (pintype "passive"))
    )
    (net (code "166") (name "Net-(D2-K)") (class "Default")
      (node (ref "C34") (pin "2") (pinfunction "2_2") (pintype "passive"))
      (node (ref "C66") (pin "2") (pinfunction "2_2") (pintype "passive"))
      (node (ref "D2") (pin "2") (pinfunction "K_2") (pintype "passive"))
      (node (ref "L3") (pin "2") (pinfunction "2_2") (pintype "passive"))
      (node (ref "U8") (pin "3") (pinfunction "SW_3") (pintype "passive"))
    )
    (net (code "167") (name "Net-(D3-A)") (class "Default")
      (node (ref "D3") (pin "1") (pinfunction "A_1") (pintype "passive"))
      (node (ref "R3") (pin "1") (pinfunction "1_1") (pintype "passive"))
    )
    (net (code "168") (name "Net-(D4-K)") (class "Default")
      (node (ref "C50") (pin "2") (pinfunction "2_2") (pintype "passive"))
      (node (ref "C55") (pin "2") (pinfunction "2_2") (pintype "passive"))
      (node (ref "D4") (pin "2") (pinfunction "K_2") (pintype "passive"))
      (node (ref "L2") (pin "2") (pinfunction "2_2") (pintype "passive"))
      (node (ref "U5") (pin "3") (pinfunction "SW_3") (pintype "passive"))
    )
    (net (code "169") (name "Net-(D5-A)") (class "Default")
      (node (ref "D5") (pin "1") (pinfunction "A_1") (pintype "passive"))
      (node (ref "R1") (pin "1") (pinfunction "1_1") (pintype "passive"))
    )
    (net (code "170") (name "Net-(S1-COMMON)") (class "Default")
      (node (ref "F1") (pin "2") (pinfunction "2_2") (pintype "passive"))
      (node (ref "S1") (pin "1") (pinfunction "COMMON_1") (pintype "passive"))
    )
    (net (code "171") (name "Net-(U1-ADC_REXT)") (class "Default")
      (node (ref "R20") (pin "2") (pinfunction "2_2") (pintype "passive"))
      (node (ref "U1") (pin "81") (pinfunction "ADC_REXT_81") (pintype "passive"))
    )
    (net (code "172") (name "Net-(U1-OTG_REXT)") (class "Default")
      (node (ref "R4") (pin "2") (pinfunction "2_2") (pintype "passive"))
      (node (ref "U1") (pin "159") (pinfunction "OTG_REXT_159") (pintype "passive"))
    )
    (net (code "173") (name "Net-(U1-USB_REXT)") (class "Default")
      (node (ref "R2") (pin "2") (pinfunction "2_2") (pintype "passive"))
      (node (ref "U1") (pin "167") (pinfunction "USB_REXT_167") (pintype "passive"))
    )
    (net (code "174") (name "Net-(U5-BS)") (class "Default")
      (node (ref "C50") (pin "1") (pinfunction "1_1") (pintype "passive"))
      (node (ref "U5") (pin "1") (pinfunction "BS_1") (pintype "passive"))
    )
    (net (code "175") (name "Net-(U5-COMP)") (class "Default")
      (node (ref "C51") (pin "2") (pinfunction "2_2") (pintype "passive"))
      (node (ref "U5") (pin "6") (pinfunction "COMP_6") (pintype "passive"))
    )
    (net (code "176") (name "Net-(U5-EN)") (class "Default")
      (node (ref "R10") (pin "2") (pinfunction "2_2") (pintype "passive"))
      (node (ref "U5") (pin "7") (pinfunction "EN_7") (pintype "passive"))
    )
    (net (code "177") (name "Net-(U5-FB)") (class "Default")
      (node (ref "R13") (pin "1") (pinfunction "1_1") (pintype "passive"))
      (node (ref "R14") (pin "2") (pinfunction "2_2") (pintype "passive"))
      (node (ref "U5") (pin "5") (pinfunction "FB_5") (pintype "passive"))
    )
    (net (code "178") (name "Net-(U5-SS)") (class "Default")
      (node (ref "C49") (pin "1") (pinfunction "1_1") (pintype "passive"))
      (node (ref "U5") (pin "8") (pinfunction "SS_8") (pintype "passive"))
    )
    (net (code "179") (name "Net-(U6-RSTI)") (class "Default")
      (node (ref "C52") (pin "1") (pinfunction "1_1") (pintype "passive"))
      (node (ref "R8") (pin "1") (pinfunction "1_1") (pintype "passive"))
      (node (ref "U6") (pin "2") (pinfunction "RSTI_2") (pintype "passive"))
    )
    (net (code "180") (name "Net-(U6-XI)") (class "Default")
      (node (ref "C63") (pin "2") (pinfunction "2_2") (pintype "passive"))
      (node (ref "U6") (pin "13") (pinfunction "XI_13") (pintype "passive"))
      (node (ref "Y3") (pin "1") (pinfunction "1_1") (pintype "passive"))
    )
    (net (code "181") (name "Net-(U6-XO)") (class "Default")
      (node (ref "C64") (pin "2") (pinfunction "2_2") (pintype "passive"))
      (node (ref "U6") (pin "14") (pinfunction "XO_14") (pintype "output"))
      (node (ref "Y3") (pin "2") (pinfunction "2_2") (pintype "passive"))
    )
    (net (code "182") (name "Net-(U8-BS)") (class "Default")
      (node (ref "C34") (pin "1") (pinfunction "1_1") (pintype "passive"))
      (node (ref "U8") (pin "1") (pinfunction "BS_1") (pintype "passive"))
    )
    (net (code "183") (name "Net-(U8-COMP)") (class "Default")
      (node (ref "C35") (pin "2") (pinfunction "2_2") (pintype "passive"))
      (node (ref "U8") (pin "6") (pinfunction "COMP_6") (pintype "passive"))
    )
    (net (code "184") (name "Net-(U8-EN)") (class "Default")
      (node (ref "R25") (pin "2") (pinfunction "2_2") (pintype "passive"))
      (node (ref "U8") (pin "7") (pinfunction "EN_7") (pintype "passive"))
    )
    (net (code "185") (name "Net-(U8-FB)") (class "Default")
      (node (ref "R28") (pin "1") (pinfunction "1_1") (pintype "passive"))
      (node (ref "R29") (pin "2") (pinfunction "2_2") (pintype "passive"))
      (node (ref "U8") (pin "5") (pinfunction "FB_5") (pintype "passive"))
    )
    (net (code "186") (name "Net-(U8-SS)") (class "Default")
      (node (ref "C33") (pin "1") (pinfunction "1_1") (pintype "passive"))
      (node (ref "U8") (pin "8") (pinfunction "SS_8") (pintype "passive"))
    )
    (net (code "187") (name "unconnected-(P5-NC-Pad9)") (class "Default")
      (node (ref "P5") (pin "9") (pinfunction "NC_9") (pintype "passive"))
    )
    (net (code "188") (name "unconnected-(P5-RST_N-Pad6)") (class "Default")
      (node (ref "P5") (pin "6") (pinfunction "RST_N_6") (pintype "passive"))
    )
    (net (code "189") (name "unconnected-(P8-CC1-PadA5)") (class "Default")
      (node (ref "P8") (pin "A5") (pinfunction "CC1_A5") (pintype "passive"))
    )
    (net (code "190") (name "unconnected-(P8-CC2-PadB5)") (class "Default")
      (node (ref "P8") (pin "B5") (pinfunction "CC2_B5") (pintype "passive"))
    )
    (net (code "191") (name "unconnected-(P8-NC-PadNC1)") (class "Default")
      (node (ref "P8") (pin "NC1") (pinfunction "NC_NC1") (pintype "passive"))
    )
    (net (code "192") (name "unconnected-(P8-NC-PadNC2)") (class "Default")
      (node (ref "P8") (pin "NC2") (pinfunction "NC_NC2") (pintype "passive"))
    )
    (net (code "193") (name "unconnected-(P8-SBU1-PadA8)") (class "Default")
      (node (ref "P8") (pin "A8") (pinfunction "SBU1_A8") (pintype "passive"))
    )
    (net (code "194") (name "unconnected-(P8-SBU2-PadB8)") (class "Default")
      (node (ref "P8") (pin "B8") (pinfunction "SBU2_B8") (pintype "passive"))
    )
    (net (code "195") (name "unconnected-(P8-SSTXN1-PadA3)") (class "Default")
      (node (ref "P8") (pin "A3") (pinfunction "SSTXN1_A3") (pintype "passive"))
    )
    (net (code "196") (name "unconnected-(P8-SSTXN1-PadB10)") (class "Default")
      (node (ref "P8") (pin "B10") (pinfunction "SSTXN1_B10") (pintype "passive"))
    )
    (net (code "197") (name "unconnected-(P8-SSTXN2-PadA10)") (class "Default")
      (node (ref "P8") (pin "A10") (pinfunction "SSTXN2_A10") (pintype "passive"))
    )
    (net (code "198") (name "unconnected-(P8-SSTXN2-PadB3)") (class "Default")
      (node (ref "P8") (pin "B3") (pinfunction "SSTXN2_B3") (pintype "passive"))
    )
    (net (code "199") (name "unconnected-(P8-SSTXP1-PadA2)") (class "Default")
      (node (ref "P8") (pin "A2") (pinfunction "SSTXP1_A2") (pintype "passive"))
    )
    (net (code "200") (name "unconnected-(P8-SSTXP1-PadB11)") (class "Default")
      (node (ref "P8") (pin "B11") (pinfunction "SSTXP1_B11") (pintype "passive"))
    )
    (net (code "201") (name "unconnected-(P8-SSTXP2-PadA11)") (class "Default")
      (node (ref "P8") (pin "A11") (pinfunction "SSTXP2_A11") (pintype "passive"))
    )
    (net (code "202") (name "unconnected-(P8-SSTXP2-PadB2)") (class "Default")
      (node (ref "P8") (pin "B2") (pinfunction "SSTXP2_B2") (pintype "passive"))
    )
    (net (code "203") (name "unconnected-(U3-NC-Pad40)") (class "Default")
      (node (ref "U3") (pin "40") (pinfunction "NC_40") (pintype "passive"))
    )
    (net (code "204") (name "unconnected-(U6-ACK#-Pad7)") (class "Default")
      (node (ref "U6") (pin "7") (pinfunction "ACK#_7") (pintype "passive"))
    )
    (net (code "205") (name "unconnected-(U6-ACT#-Pad1)") (class "Default")
      (node (ref "U6") (pin "1") (pinfunction "ACT#_1") (pintype "output"))
    )
    (net (code "206") (name "unconnected-(U6-AFD#-Pad4)") (class "Default")
      (node (ref "U6") (pin "4") (pinfunction "AFD#_4") (pintype "output"))
    )
    (net (code "207") (name "unconnected-(U6-D1-Pad16)") (class "Default")
      (node (ref "U6") (pin "16") (pinfunction "D1_16") (pintype "bidirectional"))
    )
    (net (code "208") (name "unconnected-(U6-D2-Pad17)") (class "Default")
      (node (ref "U6") (pin "17") (pinfunction "D2_17") (pintype "bidirectional"))
    )
    (net (code "209") (name "unconnected-(U6-D4-Pad19)") (class "Default")
      (node (ref "U6") (pin "19") (pinfunction "D4_19") (pintype "bidirectional"))
    )
    (net (code "210") (name "unconnected-(U6-D6-Pad21)") (class "Default")
      (node (ref "U6") (pin "21") (pinfunction "D6_21") (pintype "bidirectional"))
    )
    (net (code "211") (name "unconnected-(U6-INI#-Pad26)") (class "Default")
      (node (ref "U6") (pin "26") (pinfunction "INI#_26") (pintype "output"))
    )
    (net (code "212") (name "unconnected-(U6-SCL-Pad24)") (class "Default")
      (node (ref "U6") (pin "24") (pinfunction "SCL_24") (pintype "output"))
    )
    (net (code "213") (name "unconnected-(U6-SIN#-Pad3)") (class "Default")
      (node (ref "U6") (pin "3") (pinfunction "SIN#_3") (pintype "output"))
    )
    (net (code "214") (name "unconnected-(U6-SLCT-Pad8)") (class "Default")
      (node (ref "U6") (pin "8") (pinfunction "SLCT_8") (pintype "passive"))
    )
    (net (code "215") (name "unconnected-(U6-STB#-Pad25)") (class "Default")
      (node (ref "U6") (pin "25") (pinfunction "STB#_25") (pintype "output"))
    )
  )
)
